# mk312_smt_main_V2a.net
KiCad netlist of a schematic drawn in EAGLE
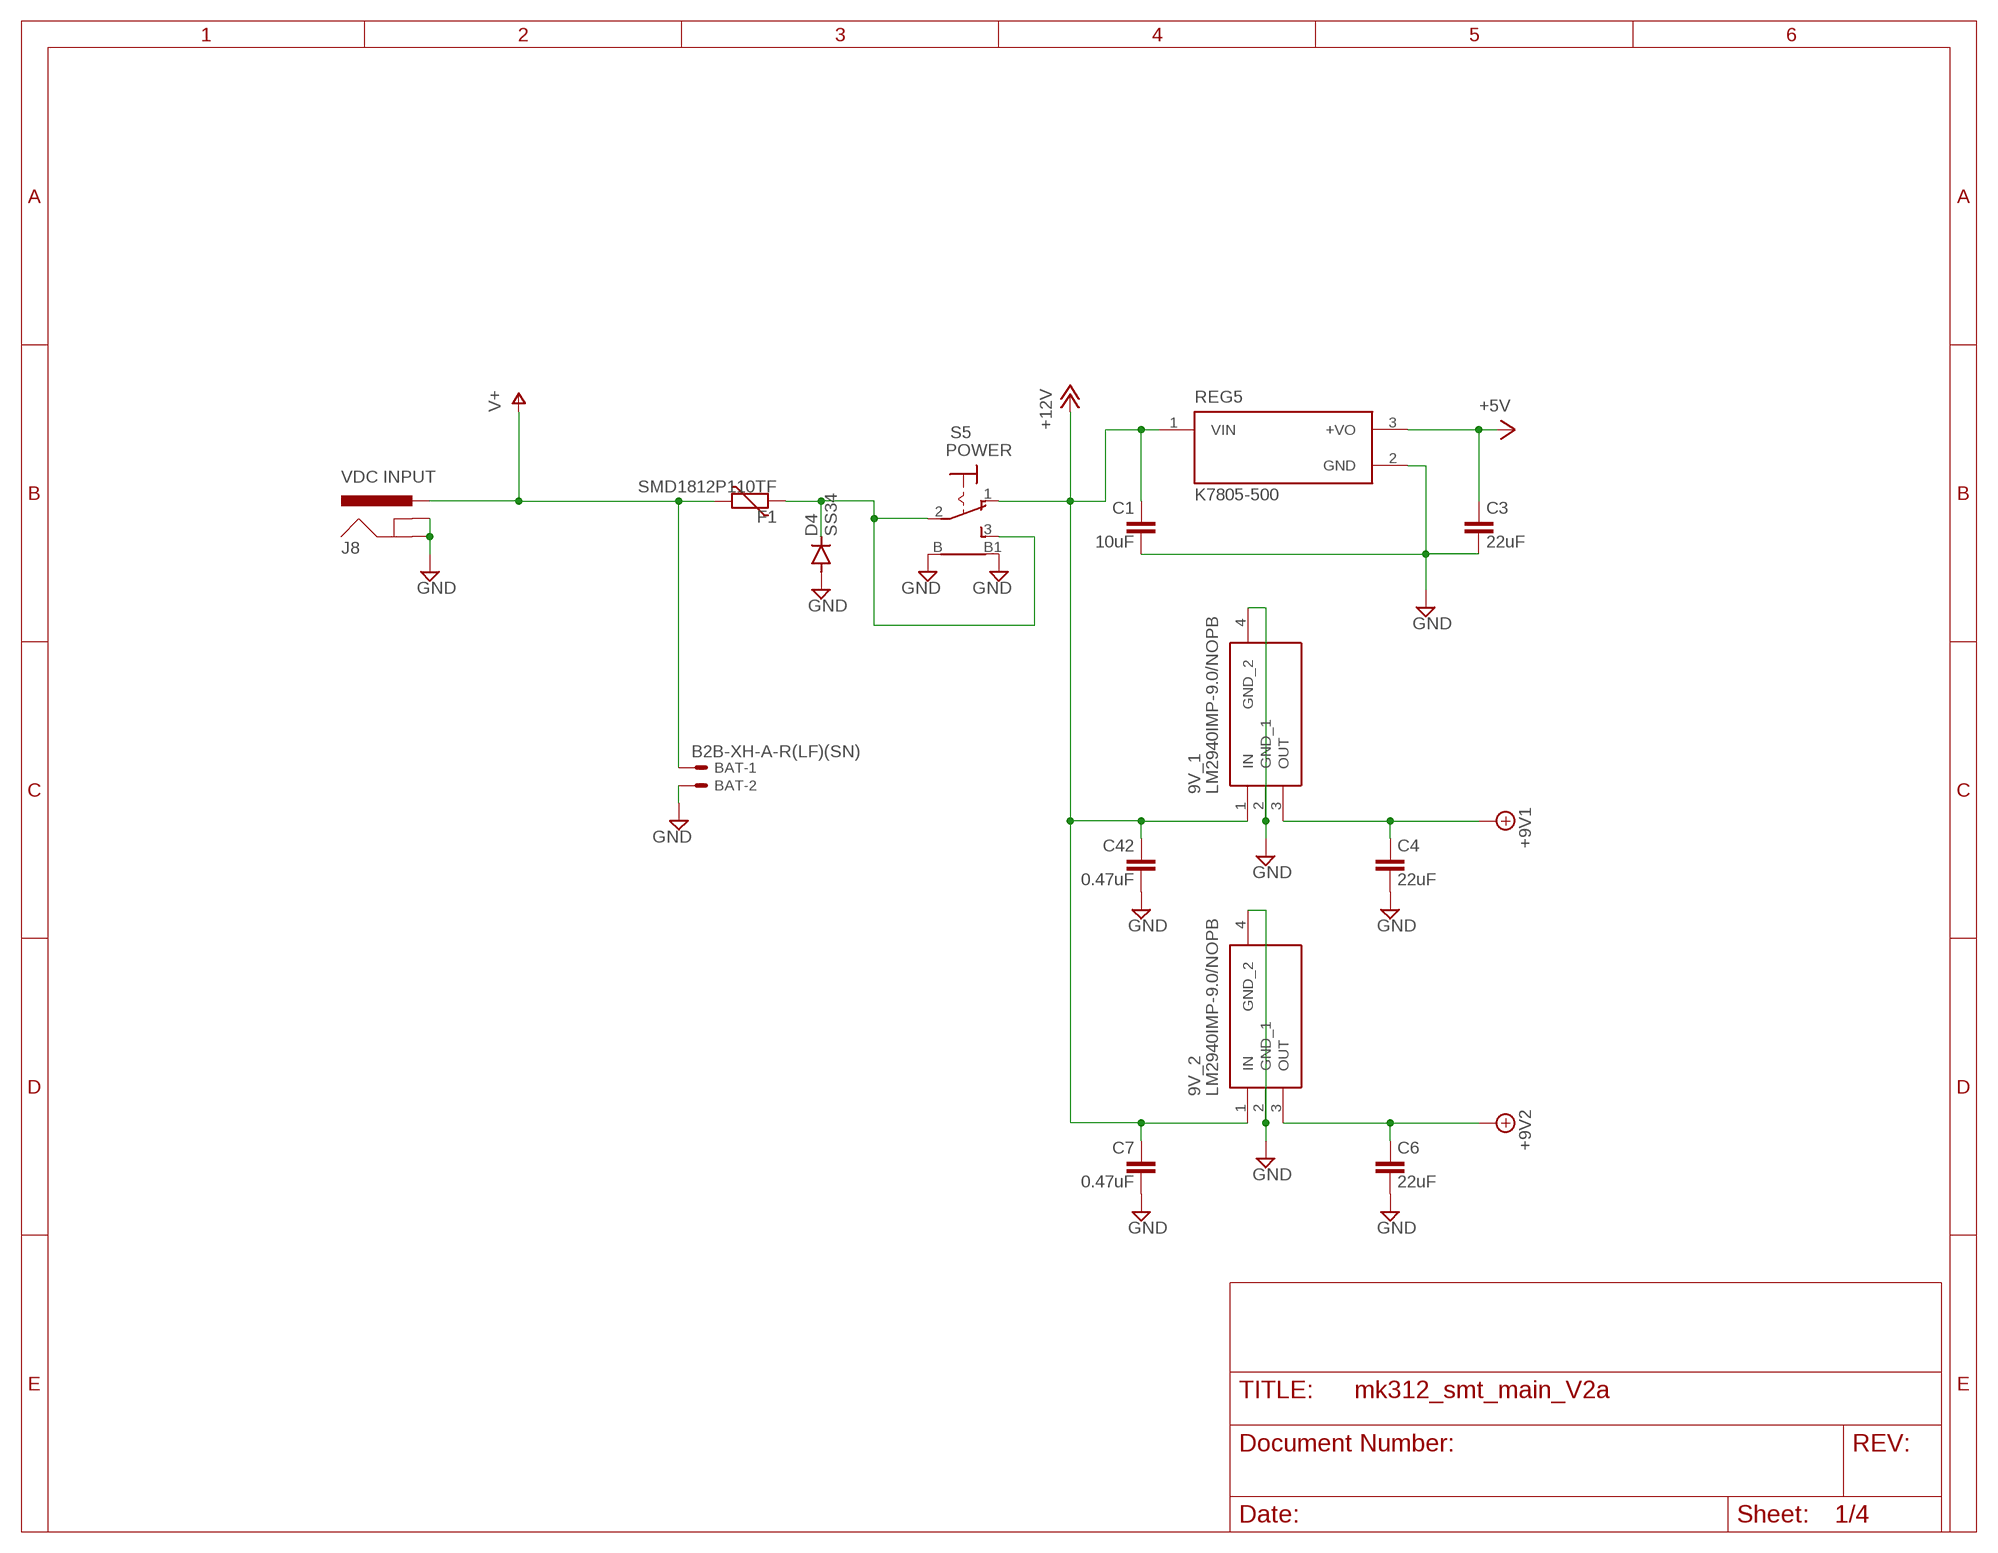
[diagram p0: schematic, sheet 1]
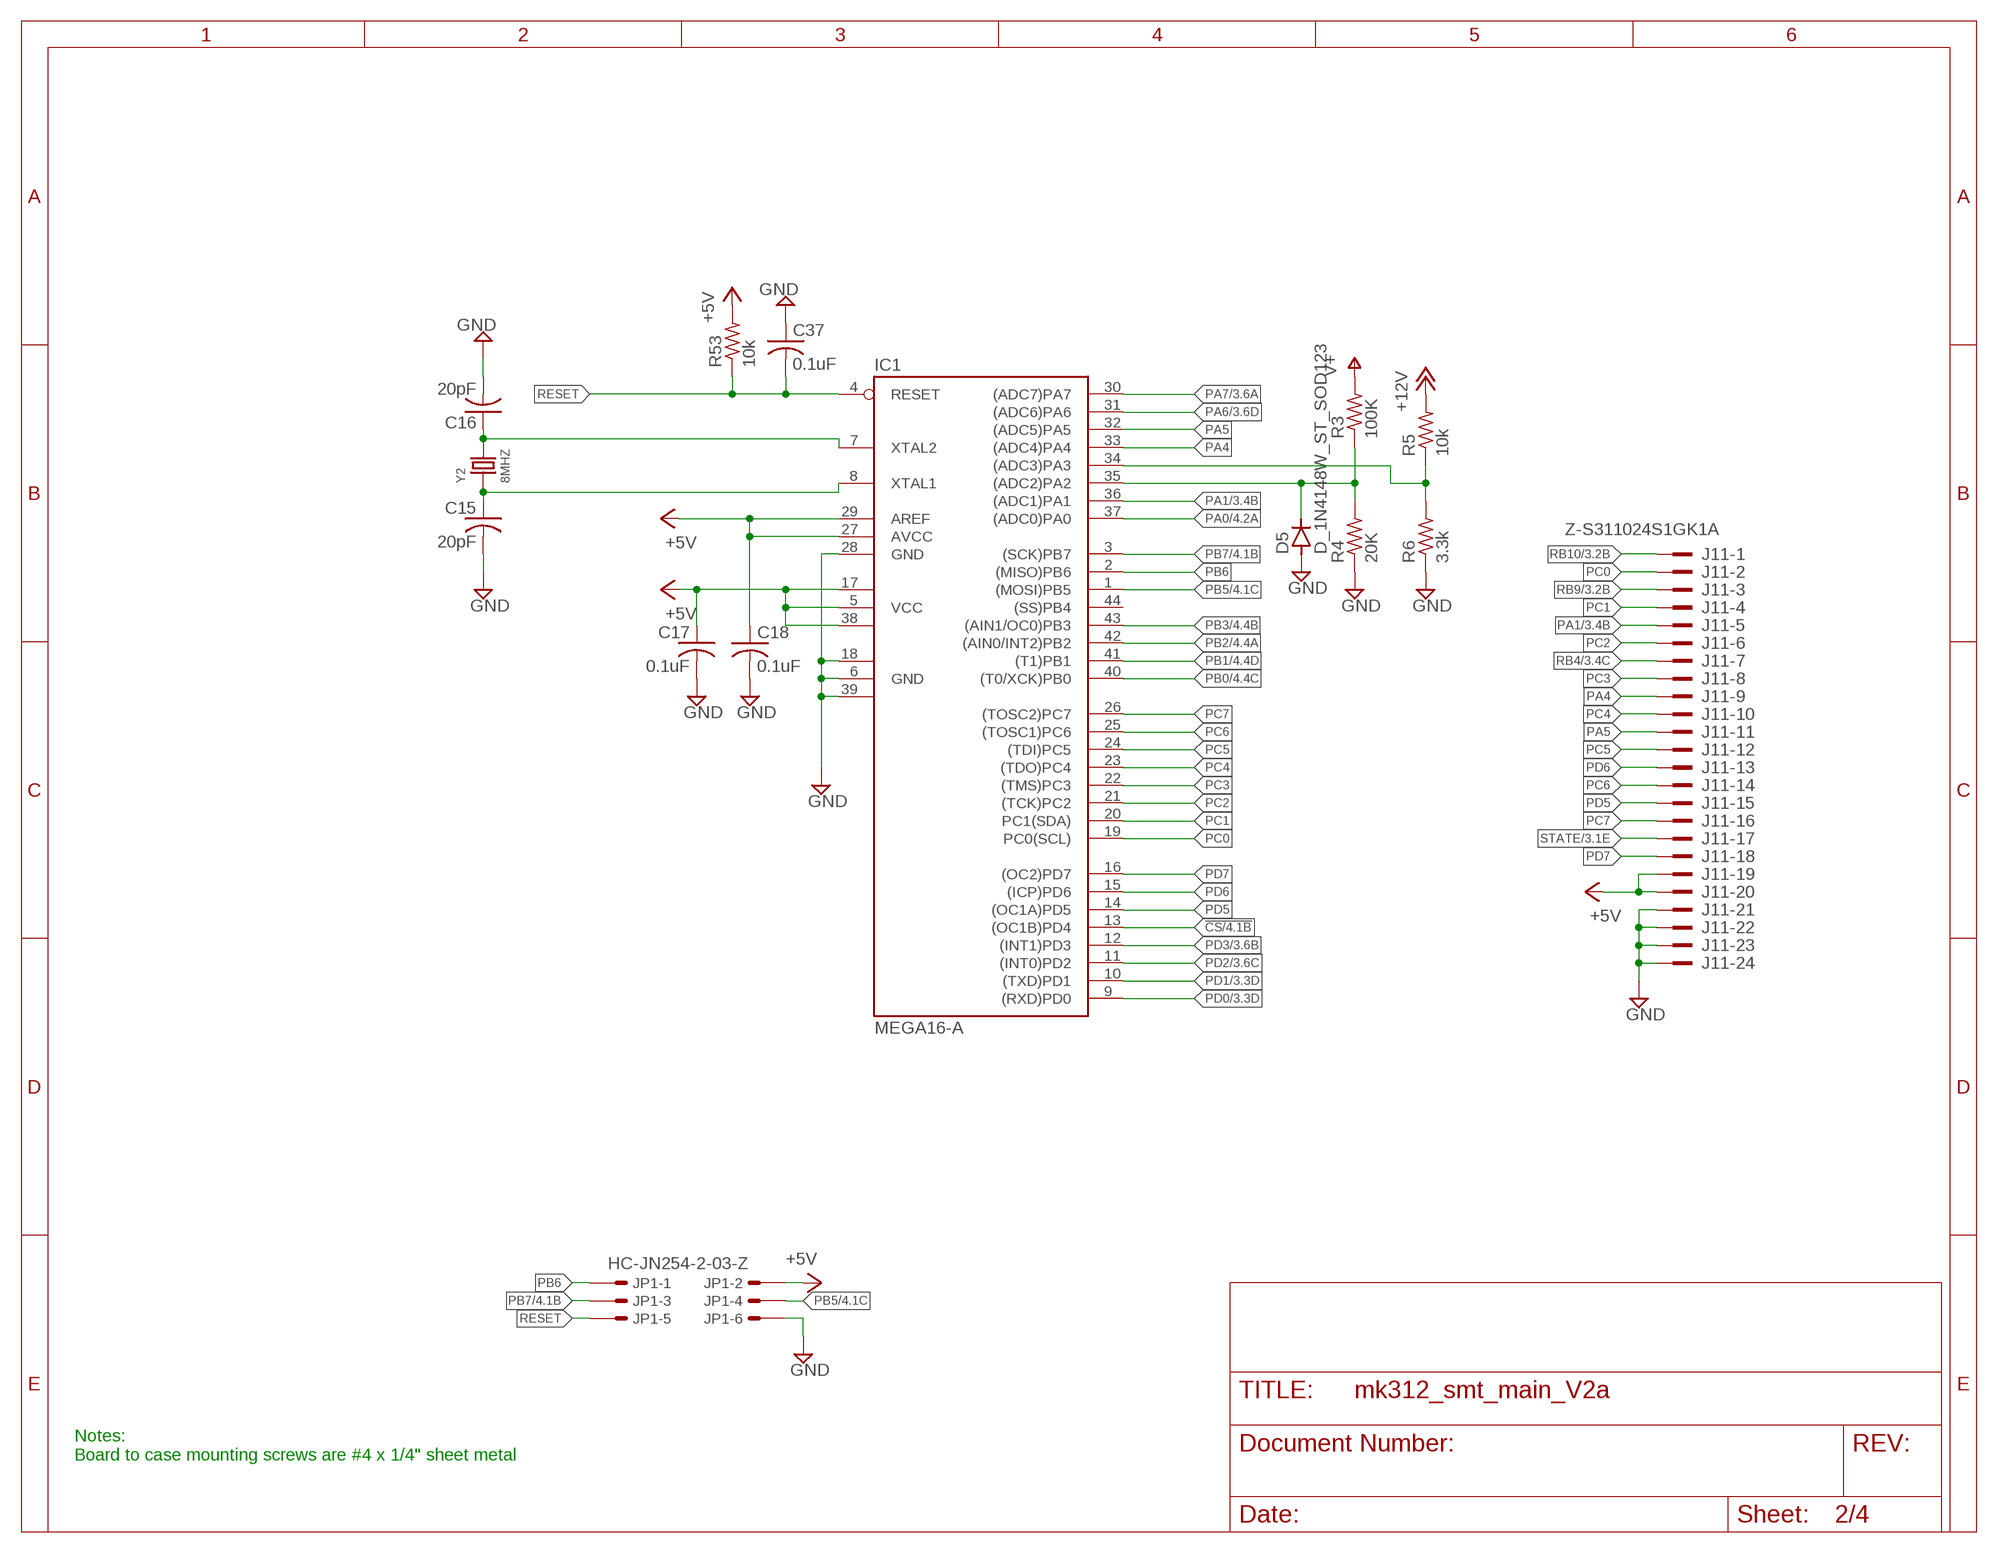
[diagram p1: schematic, sheet 2]
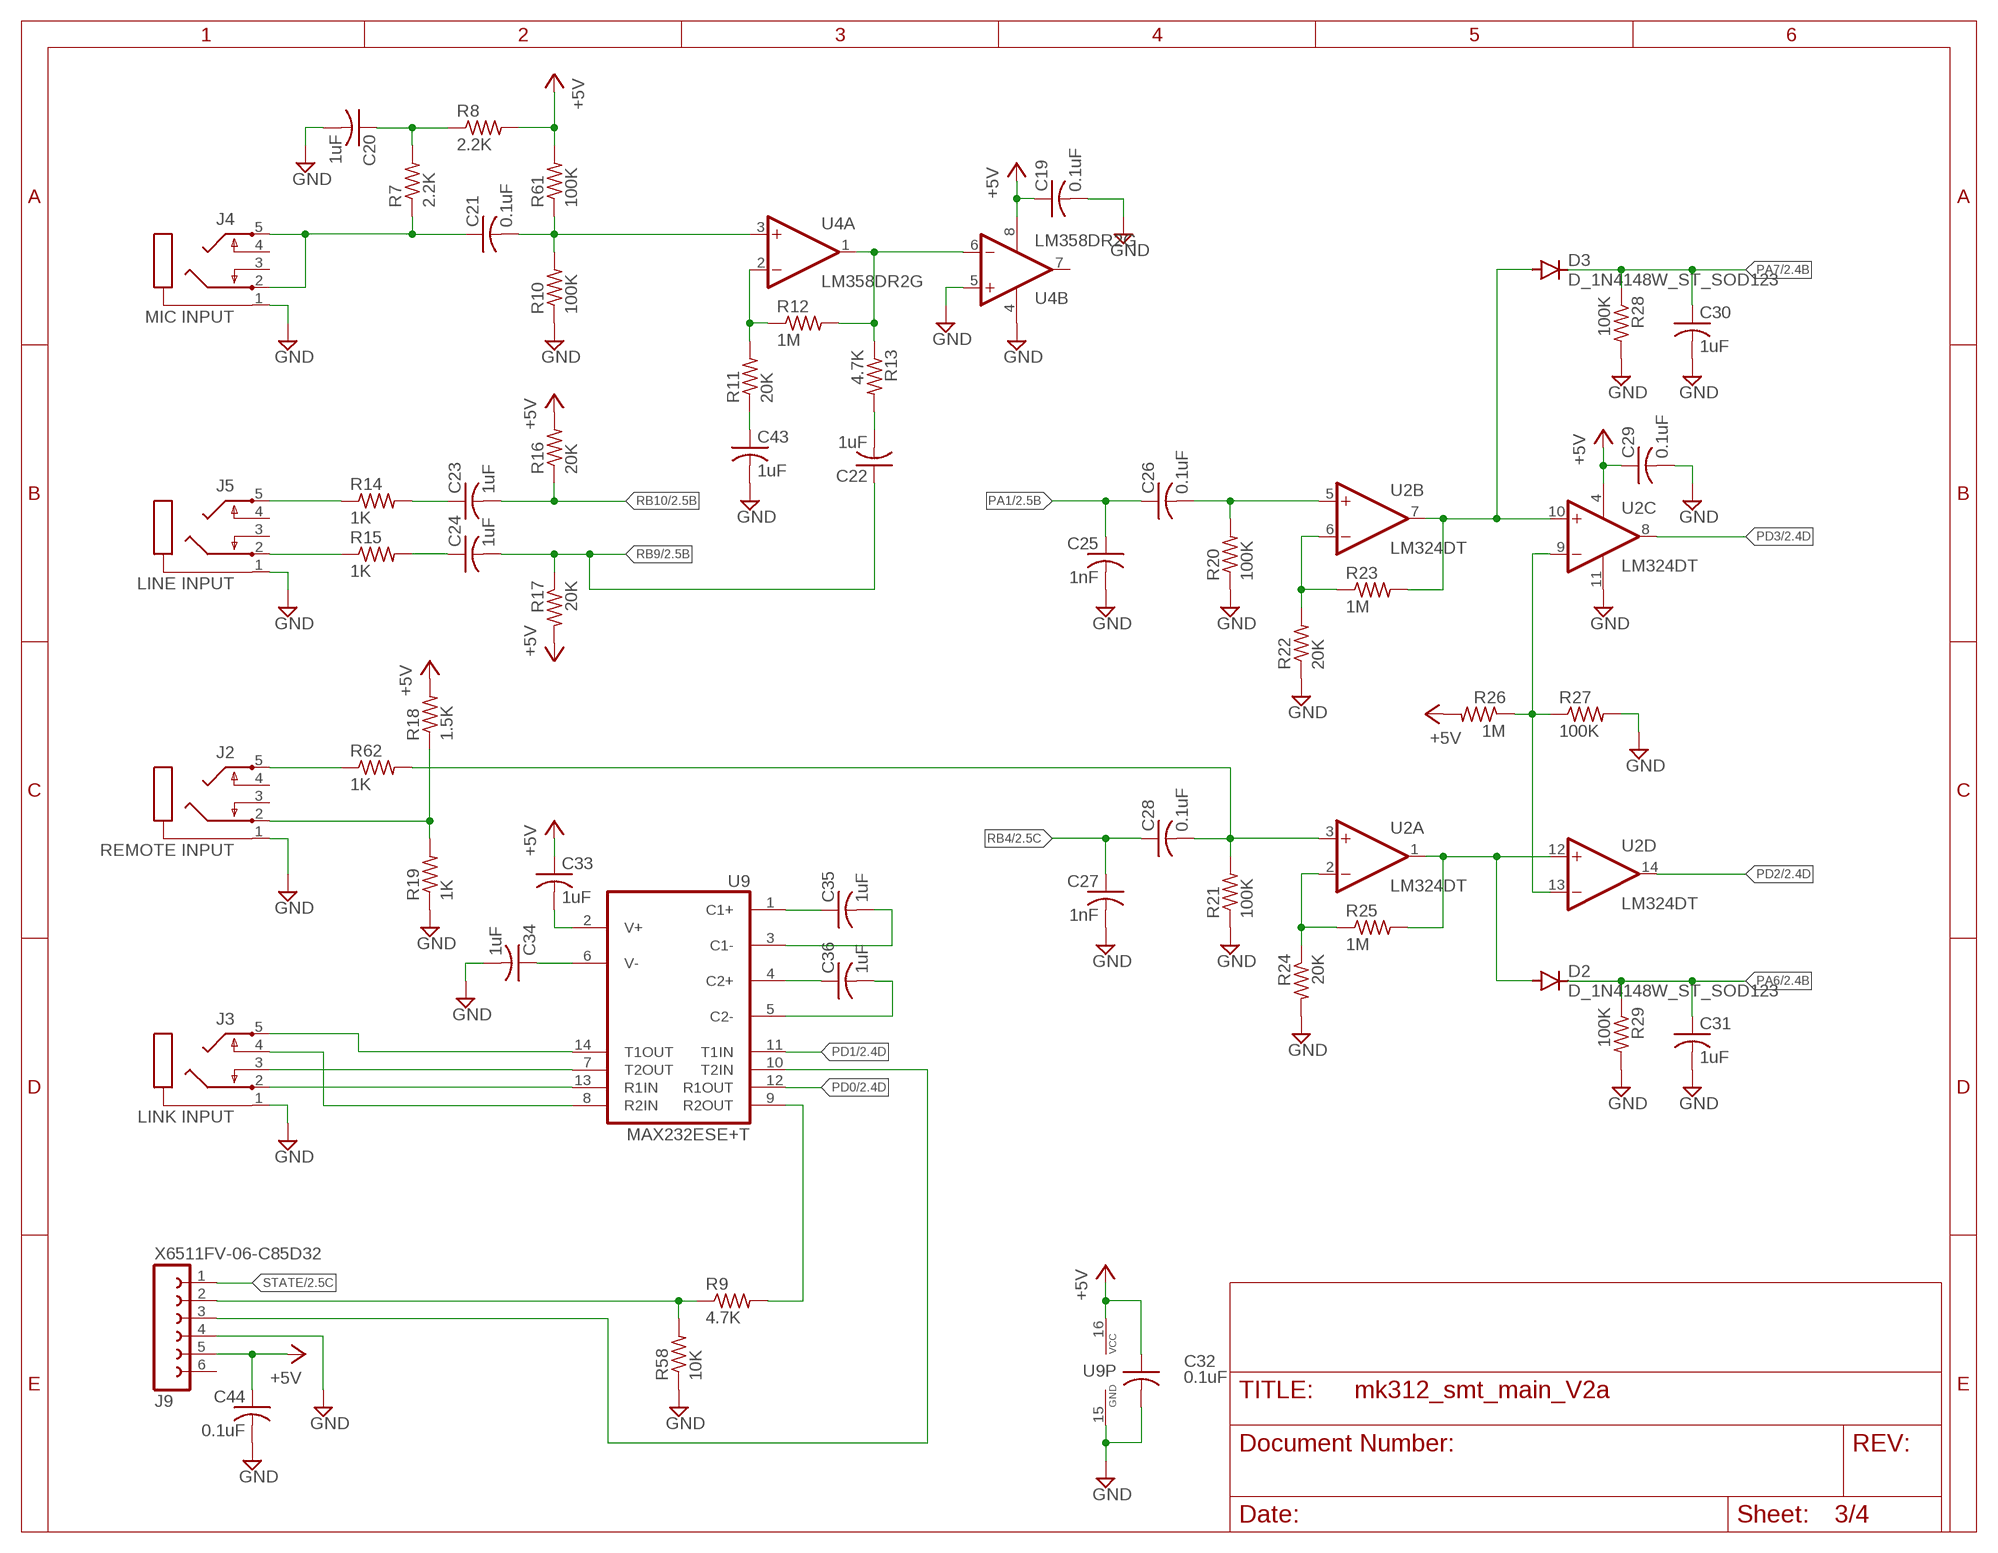
[diagram p2: schematic, sheet 3]
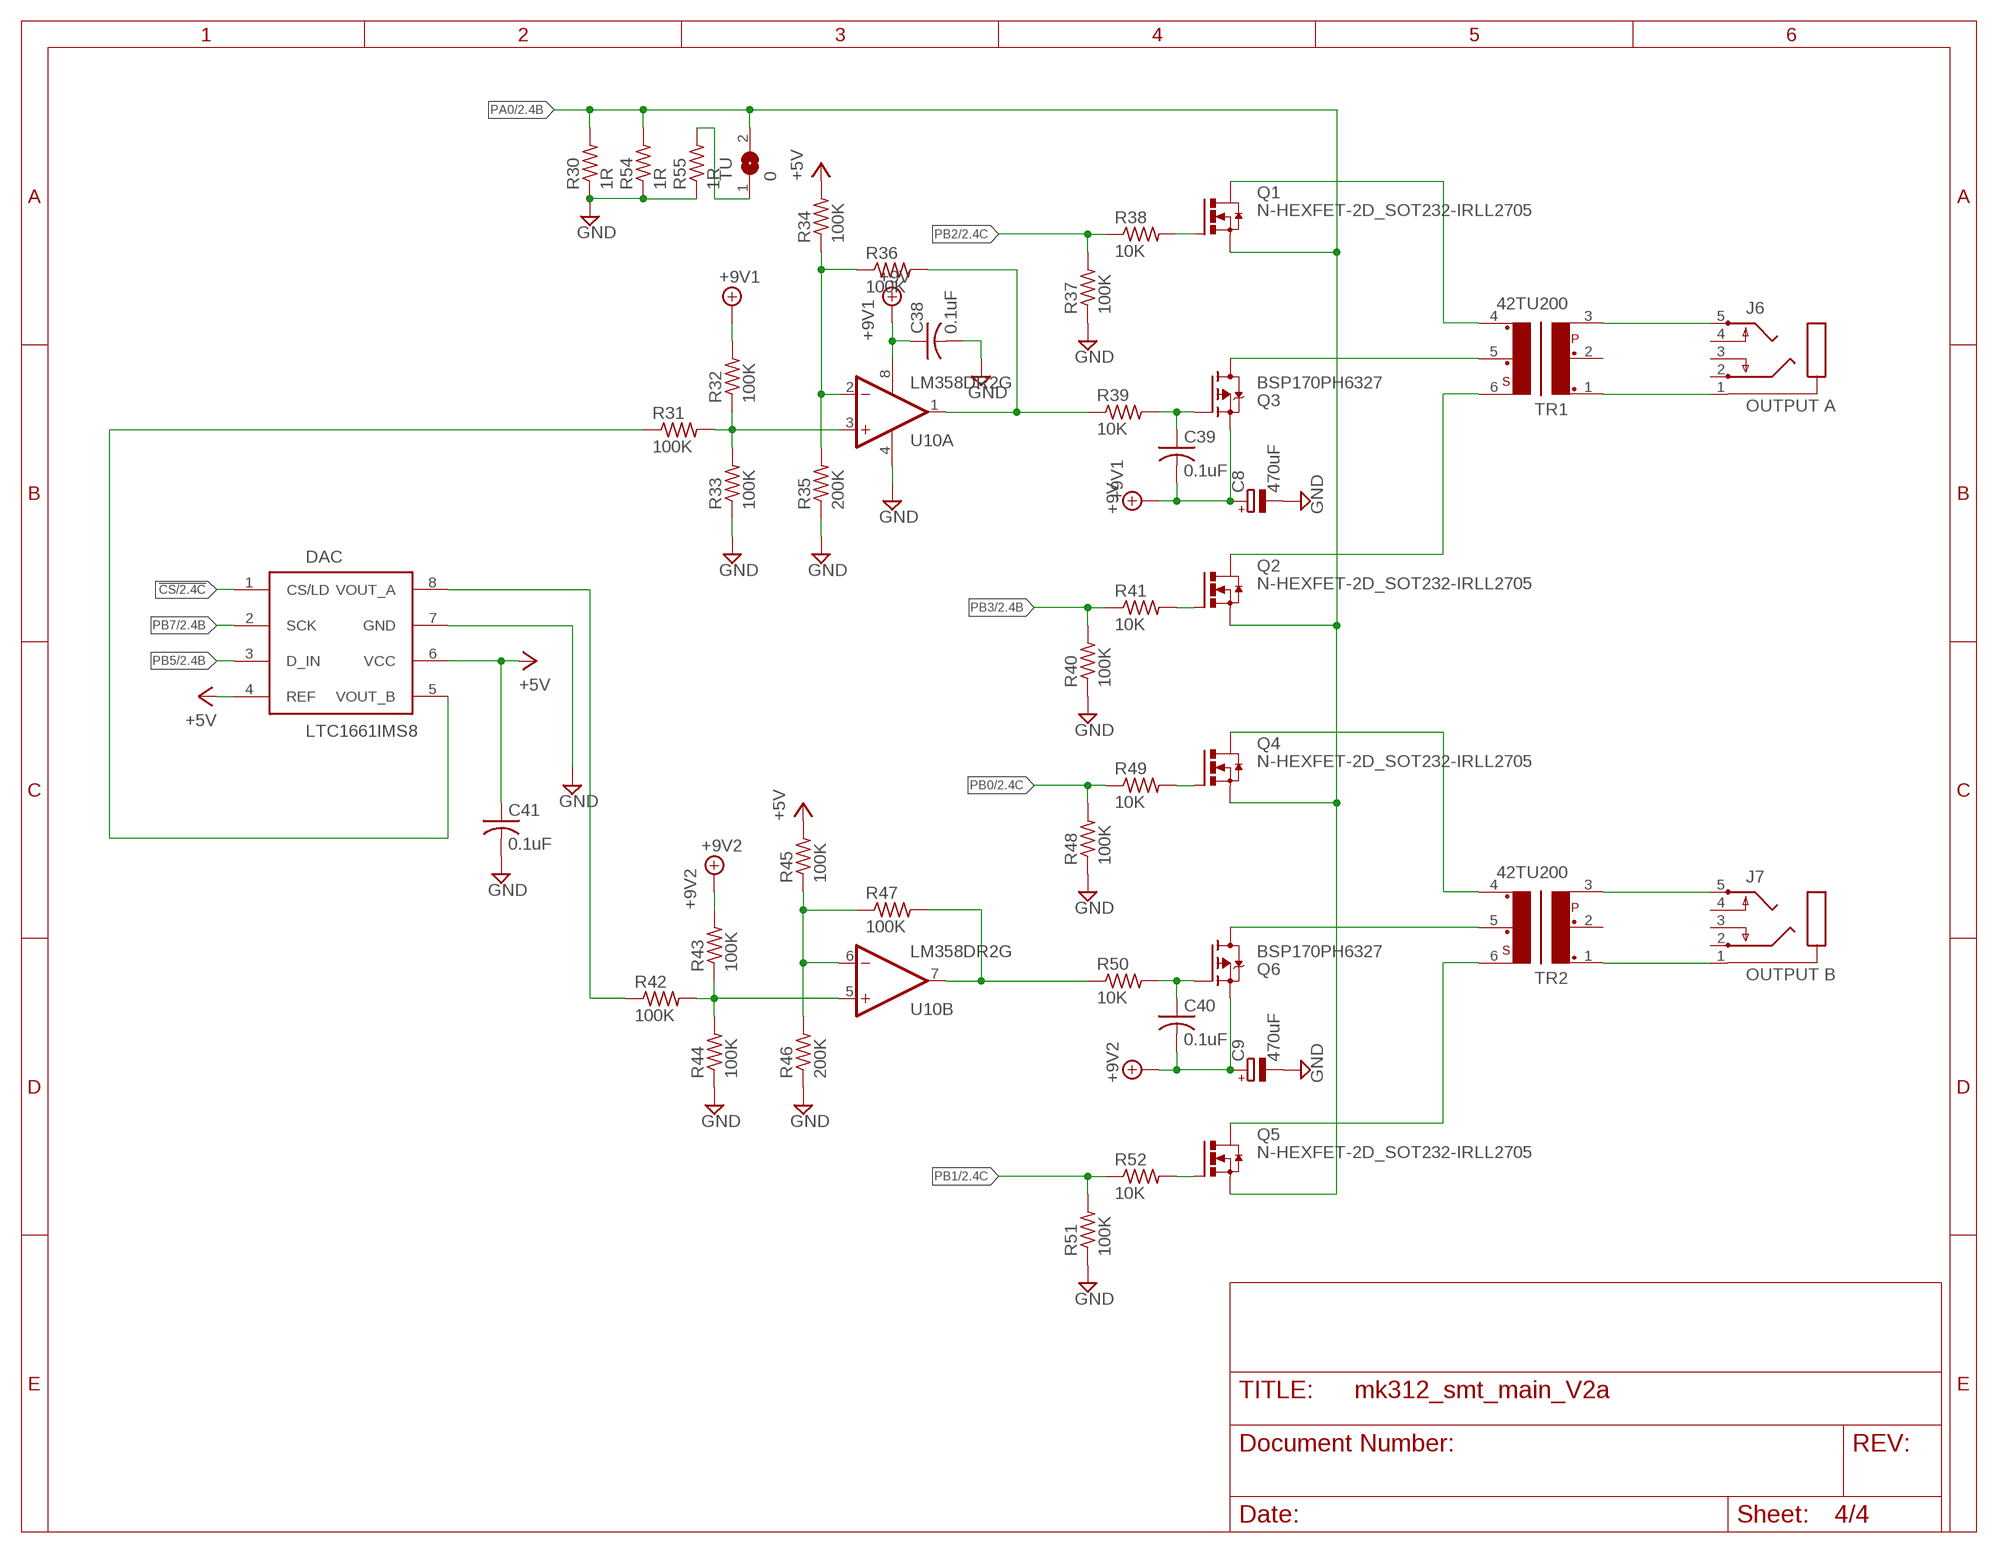
[diagram p3: schematic, sheet 4]

(export (version "E")
  (design (tool "Eeschema 10.0.6"))
  (components
    (comp (ref "C15")
      (value "20pF")
      (footprint "eagle-import:C0603")
      (libsource (lib "eagle-import") (part "C-USC0603"))
    )
    (comp (ref "C16")
      (value "20pF")
      (footprint "eagle-import:C0603")
      (libsource (lib "eagle-import") (part "C-USC0603"))
    )
    (comp (ref "C17")
      (value "0.1uF")
      (footprint "eagle-import:C0805")
      (libsource (lib "eagle-import") (part "C-USC0805"))
    )
    (comp (ref "C18")
      (value "0.1uF")
      (footprint "eagle-import:C0805")
      (libsource (lib "eagle-import") (part "C-USC0805"))
    )
    (comp (ref "C37")
      (value "0.1uF")
      (footprint "eagle-import:C0805")
      (libsource (lib "eagle-import") (part "rcl_334_C-USC0805"))
    )
    (comp (ref "D5")
      (value "D_1N4148W_ST_SOD123")
      (footprint "eagle-import:SOD123")
      (fields (field (name "LCSC_PART") "C81598"))
      (libsource (lib "eagle-import") (part "D__SOD1231N4148W_ST"))
    )
    (comp (ref "IC1")
      (value "MEGA16-A")
      (footprint "eagle-import:TQFP44")
      (fields (field (name "MPN") "ATMEGA16-16AU"))
      (libsource (lib "eagle-import") (part "MEGA16-A"))
    )
    (comp (ref "J11")
      (value "Z-S311024S1GK1A")
      (footprint "eagle-import:PAK100_2500-24")
      (libsource (lib "eagle-import") (part "2524-"))
    )
    (comp (ref "JP1")
      (value "HC-JN254-2-03-Z")
      (footprint "eagle-import:057-006-1")
      (libsource (lib "eagle-import") (part "057-006-1"))
    )
    (comp (ref "R3")
      (value "100K")
      (footprint "eagle-import:R0805")
      (libsource (lib "eagle-import") (part "R-US_R0805"))
    )
    (comp (ref "R4")
      (value "20K")
      (footprint "eagle-import:R0805")
      (libsource (lib "eagle-import") (part "R-US_R0805"))
    )
    (comp (ref "R5")
      (value "10k")
      (footprint "eagle-import:R0805")
      (libsource (lib "eagle-import") (part "R-US_R0805"))
    )
    (comp (ref "R6")
      (value "3.3k")
      (footprint "eagle-import:R0805")
      (libsource (lib "eagle-import") (part "R-US_R0805"))
    )
    (comp (ref "R53")
      (value "10k")
      (footprint "eagle-import:R0805")
      (libsource (lib "eagle-import") (part "rcl_334_R-US_R0805"))
    )
    (comp (ref "Y2")
      (value "8MHZ")
      (footprint "eagle-import:X2-SMD-5.0X3.2X1.3MM")
      (fields (field (name "MPN") "5032/2P"))
      (libsource (lib "eagle-import") (part "SMD-CRYSTAL-8MHZ-20PF-20PPM(2P-5.0X3.2MM)"))
    )
    (comp (ref "C19")
      (value "0.1uF")
      (footprint "eagle-import:C0805")
      (libsource (lib "eagle-import") (part "C-USC0805"))
    )
    (comp (ref "C20")
      (value "1uF")
      (footprint "eagle-import:C0805")
      (libsource (lib "eagle-import") (part "C-USC0805"))
    )
    (comp (ref "C21")
      (value "0.1uF")
      (footprint "eagle-import:C0805")
      (libsource (lib "eagle-import") (part "C-USC0805"))
    )
    (comp (ref "C22")
      (value "1uF")
      (footprint "eagle-import:C0805")
      (libsource (lib "eagle-import") (part "C-USC0805"))
    )
    (comp (ref "C23")
      (value "1uF")
      (footprint "eagle-import:C0805")
      (libsource (lib "eagle-import") (part "C-USC0805"))
    )
    (comp (ref "C24")
      (value "1uF")
      (footprint "eagle-import:C0805")
      (libsource (lib "eagle-import") (part "C-USC0805"))
    )
    (comp (ref "C25")
      (value "1nF")
      (footprint "eagle-import:C0805")
      (libsource (lib "eagle-import") (part "C-USC0805"))
    )
    (comp (ref "C26")
      (value "0.1uF")
      (footprint "eagle-import:C0805")
      (libsource (lib "eagle-import") (part "C-USC0805"))
    )
    (comp (ref "C27")
      (value "1nF")
      (footprint "eagle-import:C0805")
      (libsource (lib "eagle-import") (part "C-USC0805"))
    )
    (comp (ref "C28")
      (value "0.1uF")
      (footprint "eagle-import:C0805")
      (libsource (lib "eagle-import") (part "C-USC0805"))
    )
    (comp (ref "C29")
      (value "0.1uF")
      (footprint "eagle-import:C0805")
      (libsource (lib "eagle-import") (part "C-USC0805"))
    )
    (comp (ref "C30")
      (value "1uF")
      (footprint "eagle-import:C0805")
      (libsource (lib "eagle-import") (part "C-USC0805"))
    )
    (comp (ref "C31")
      (value "1uF")
      (footprint "eagle-import:C0805")
      (libsource (lib "eagle-import") (part "C-USC0805"))
    )
    (comp (ref "C32")
      (value "0.1uF")
      (footprint "eagle-import:C0805")
      (libsource (lib "eagle-import") (part "C-USC0805"))
    )
    (comp (ref "C33")
      (value "1uF")
      (footprint "eagle-import:C0805")
      (libsource (lib "eagle-import") (part "C-USC0805"))
    )
    (comp (ref "C34")
      (value "1uF")
      (footprint "eagle-import:C0805")
      (libsource (lib "eagle-import") (part "C-USC0805"))
    )
    (comp (ref "C35")
      (value "1uF")
      (footprint "eagle-import:C0805")
      (libsource (lib "eagle-import") (part "C-USC0805"))
    )
    (comp (ref "C36")
      (value "1uF")
      (footprint "eagle-import:C0805")
      (libsource (lib "eagle-import") (part "C-USC0805"))
    )
    (comp (ref "C43")
      (value "1uF")
      (footprint "eagle-import:C0805")
      (libsource (lib "eagle-import") (part "C-USC0805"))
    )
    (comp (ref "C44")
      (value "0.1uF")
      (footprint "eagle-import:C0805")
      (libsource (lib "eagle-import") (part "C-USC0805"))
    )
    (comp (ref "D2")
      (value "D_1N4148W_ST_SOD123")
      (footprint "eagle-import:SOD123")
      (fields (field (name "LCSC_PART") "C81598"))
      (libsource (lib "eagle-import") (part "D__SOD1231N4148W_ST"))
    )
    (comp (ref "D3")
      (value "D_1N4148W_ST_SOD123")
      (footprint "eagle-import:SOD123")
      (fields (field (name "LCSC_PART") "C81598"))
      (libsource (lib "eagle-import") (part "D__SOD1231N4148W_ST"))
    )
    (comp (ref "J2")
      (value "REMOTE INPUT")
      (footprint "eagle-import:PJ-3062")
      (libsource (lib "eagle-import") (part "STEREOJACKPJ-3062"))
    )
    (comp (ref "J3")
      (value "LINK INPUT")
      (footprint "eagle-import:PJ-3062")
      (libsource (lib "eagle-import") (part "STEREOJACKPJ-3062"))
    )
    (comp (ref "J4")
      (value "MIC INPUT")
      (footprint "eagle-import:PJ-3062")
      (libsource (lib "eagle-import") (part "STEREOJACKPJ-3062"))
    )
    (comp (ref "J5")
      (value "LINE INPUT")
      (footprint "eagle-import:PJ-3062")
      (libsource (lib "eagle-import") (part "STEREOJACKPJ-3062"))
    )
    (comp (ref "J9")
      (value "X6511FV-06-C85D32")
      (footprint "eagle-import:FE06")
      (libsource (lib "eagle-import") (part "FE06-1"))
    )
    (comp (ref "R7")
      (value "2.2K")
      (footprint "eagle-import:R0805")
      (libsource (lib "eagle-import") (part "R-US_R0805"))
    )
    (comp (ref "R8")
      (value "2.2K")
      (footprint "eagle-import:R0805")
      (libsource (lib "eagle-import") (part "R-US_R0805"))
    )
    (comp (ref "R9")
      (value "4.7K")
      (footprint "eagle-import:R0805")
      (libsource (lib "eagle-import") (part "R-US_R0805"))
    )
    (comp (ref "R10")
      (value "100K")
      (footprint "eagle-import:R0805")
      (libsource (lib "eagle-import") (part "R-US_R0805"))
    )
    (comp (ref "R11")
      (value "20K")
      (footprint "eagle-import:R0805")
      (libsource (lib "eagle-import") (part "R-US_R0805"))
    )
    (comp (ref "R12")
      (value "1M")
      (footprint "eagle-import:R0805")
      (libsource (lib "eagle-import") (part "R-US_R0805"))
    )
    (comp (ref "R13")
      (value "4.7K")
      (footprint "eagle-import:R0805")
      (libsource (lib "eagle-import") (part "R-US_R0805"))
    )
    (comp (ref "R14")
      (value "1K")
      (footprint "eagle-import:R0805")
      (libsource (lib "eagle-import") (part "R-US_R0805"))
    )
    (comp (ref "R15")
      (value "1K")
      (footprint "eagle-import:R0805")
      (libsource (lib "eagle-import") (part "R-US_R0805"))
    )
    (comp (ref "R16")
      (value "20K")
      (footprint "eagle-import:R0805")
      (libsource (lib "eagle-import") (part "R-US_R0805"))
    )
    (comp (ref "R17")
      (value "20K")
      (footprint "eagle-import:R0805")
      (libsource (lib "eagle-import") (part "R-US_R0805"))
    )
    (comp (ref "R18")
      (value "1.5K")
      (footprint "eagle-import:R0805")
      (libsource (lib "eagle-import") (part "R-US_R0805"))
    )
    (comp (ref "R19")
      (value "1K")
      (footprint "eagle-import:R0805")
      (libsource (lib "eagle-import") (part "R-US_R0805"))
    )
    (comp (ref "R20")
      (value "100K")
      (footprint "eagle-import:R0805")
      (libsource (lib "eagle-import") (part "R-US_R0805"))
    )
    (comp (ref "R21")
      (value "100K")
      (footprint "eagle-import:R0805")
      (libsource (lib "eagle-import") (part "R-US_R0805"))
    )
    (comp (ref "R22")
      (value "20K")
      (footprint "eagle-import:R0805")
      (libsource (lib "eagle-import") (part "R-US_R0805"))
    )
    (comp (ref "R23")
      (value "1M")
      (footprint "eagle-import:R0805")
      (libsource (lib "eagle-import") (part "R-US_R0805"))
    )
    (comp (ref "R24")
      (value "20K")
      (footprint "eagle-import:R0805")
      (libsource (lib "eagle-import") (part "R-US_R0805"))
    )
    (comp (ref "R25")
      (value "1M")
      (footprint "eagle-import:R0805")
      (libsource (lib "eagle-import") (part "R-US_R0805"))
    )
    (comp (ref "R26")
      (value "1M")
      (footprint "eagle-import:R0805")
      (libsource (lib "eagle-import") (part "R-US_R0805"))
    )
    (comp (ref "R27")
      (value "100K")
      (footprint "eagle-import:R0805")
      (libsource (lib "eagle-import") (part "R-US_R0805"))
    )
    (comp (ref "R28")
      (value "100K")
      (footprint "eagle-import:R0805")
      (libsource (lib "eagle-import") (part "R-US_R0805"))
    )
    (comp (ref "R29")
      (value "100K")
      (footprint "eagle-import:R0805")
      (libsource (lib "eagle-import") (part "R-US_R0805"))
    )
    (comp (ref "R58")
      (value "10K")
      (footprint "eagle-import:R0805")
      (libsource (lib "eagle-import") (part "R-US_R0805"))
    )
    (comp (ref "R61")
      (value "100K")
      (footprint "eagle-import:R0805")
      (libsource (lib "eagle-import") (part "R-US_R0805"))
    )
    (comp (ref "R62")
      (value "1K")
      (footprint "eagle-import:R0805")
      (libsource (lib "eagle-import") (part "R-US_R0805"))
    )
    (comp (ref "U2")
      (value "LM324DT")
      (footprint "eagle-import:SO14")
      (libsource (lib "eagle-import") (part "LM324D"))
    )
    (comp (ref "U4")
      (value "LM358DR2G")
      (footprint "eagle-import:SO08")
      (libsource (lib "eagle-import") (part "LM358D"))
    )
    (comp (ref "U9")
      (value "MAX232ESE+T")
      (footprint "eagle-import:SOP-16")
      (libsource (lib "eagle-import") (part "MAX232ECWESOP16"))
    )
    (comp (ref "9V_1")
      (value "LM2940IMP-9.0/NOPB")
      (footprint "eagle-import:SOT230P700X180-4N")
      (fields (field (name "MOUSER_PART_NUMBER") "926-LM2940IMP90NOPB"))
      (libsource (lib "eagle-import") (part "LM2940IMP-9.0_NOPB"))
    )
    (comp (ref "9V_2")
      (value "LM2940IMP-9.0/NOPB")
      (footprint "eagle-import:SOT230P700X180-4N")
      (fields (field (name "MOUSER_PART_NUMBER") "926-LM2940IMP90NOPB"))
      (libsource (lib "eagle-import") (part "LM2940IMP-9.0_NOPB"))
    )
    (comp (ref "BAT")
      (value "B2B-XH-A-R(LF)(SN)")
      (footprint "eagle-import:JST-XH-02-PACKAGE-LONG-PAD")
      (libsource (lib "eagle-import") (part "JST-XH-02-PIN-LONG-PAD"))
    )
    (comp (ref "C1")
      (value "10uF")
      (footprint "eagle-import:C0805")
      (libsource (lib "eagle-import") (part "C-EUC0805"))
    )
    (comp (ref "C3")
      (value "22uF")
      (footprint "eagle-import:C1206")
      (libsource (lib "eagle-import") (part "C-EUC1206"))
    )
    (comp (ref "C4")
      (value "22uF")
      (footprint "eagle-import:C1206")
      (libsource (lib "eagle-import") (part "C-EUC1206"))
    )
    (comp (ref "C6")
      (value "22uF")
      (footprint "eagle-import:C1206")
      (libsource (lib "eagle-import") (part "C-EUC1206"))
    )
    (comp (ref "C7")
      (value "0.47uF")
      (footprint "eagle-import:C0805")
      (libsource (lib "eagle-import") (part "C-EUC0805"))
    )
    (comp (ref "C42")
      (value "0.47uF")
      (footprint "eagle-import:C0805")
      (libsource (lib "eagle-import") (part "C-EUC0805"))
    )
    (comp (ref "D4")
      (value "SS34")
      (footprint "eagle-import:SMA")
      (libsource (lib "eagle-import") (part "S1M"))
    )
    (comp (ref "F1")
      (value "SMD1812P110TF")
      (footprint "eagle-import:CT_CN1812")
      (libsource (lib "eagle-import") (part "VARISTORCN1812"))
    )
    (comp (ref "J8")
      (value "VDC INPUT")
      (footprint "eagle-import:POWER_JACK_SLOT")
      (libsource (lib "eagle-import") (part "POWER_JACKSLT"))
    )
    (comp (ref "REG5")
      (value "K7805-500")
      (footprint "eagle-import:CONV_K7809M-1000R3")
      (fields (field (name "MF") "Mornsun America, LLC") (field (name "MP") "K7809M-1000R3"))
      (libsource (lib "eagle-import") (part "K7809M-1000R3"))
    )
    (comp (ref "S5")
      (value "POWER")
      (footprint "eagle-import:LPV-1")
      (libsource (lib "eagle-import") (part "LPV-1"))
    )
    (comp (ref "C8")
      (value "470uF")
      (footprint "eagle-import:150CLZ-1010")
      (libsource (lib "eagle-import") (part "CPOL-EU150CLZ-1010"))
    )
    (comp (ref "C9")
      (value "470uF")
      (footprint "eagle-import:150CLZ-1010")
      (libsource (lib "eagle-import") (part "CPOL-EU150CLZ-1010"))
    )
    (comp (ref "C38")
      (value "0.1uF")
      (footprint "eagle-import:C0805")
      (libsource (lib "eagle-import") (part "C-USC0805"))
    )
    (comp (ref "C39")
      (value "0.1uF")
      (footprint "eagle-import:C0805")
      (libsource (lib "eagle-import") (part "C-USC0805"))
    )
    (comp (ref "C40")
      (value "0.1uF")
      (footprint "eagle-import:C0805")
      (libsource (lib "eagle-import") (part "C-USC0805"))
    )
    (comp (ref "C41")
      (value "0.1uF")
      (footprint "eagle-import:C0805")
      (libsource (lib "eagle-import") (part "C-USC0805"))
    )
    (comp (ref "DAC")
      (value "LTC1661IMS8")
      (footprint "eagle-import:MSOP8")
      (libsource (lib "eagle-import") (part "LTC1661IMS8"))
    )
    (comp (ref "J6")
      (value "OUTPUT A")
      (footprint "eagle-import:PJ-3062")
      (libsource (lib "eagle-import") (part "STEREOJACKPJ-3062"))
    )
    (comp (ref "J7")
      (value "OUTPUT B")
      (footprint "eagle-import:PJ-3062")
      (libsource (lib "eagle-import") (part "STEREOJACKPJ-3062"))
    )
    (comp (ref "Q1")
      (value "N-HEXFET-2D_SOT232-IRLL2705")
      (footprint "eagle-import:SOT223")
      (libsource (lib "eagle-import") (part "N-HEXFET-2D_?-SOT232IRLL2705"))
    )
    (comp (ref "Q2")
      (value "N-HEXFET-2D_SOT232-IRLL2705")
      (footprint "eagle-import:SOT223")
      (libsource (lib "eagle-import") (part "N-HEXFET-2D_?-SOT232IRLL2705"))
    )
    (comp (ref "Q3")
      (value "BSP170PH6327")
      (footprint "eagle-import:SOT230P700X180-4N")
      (libsource (lib "eagle-import") (part "IRFL9014TRPBF"))
    )
    (comp (ref "Q4")
      (value "N-HEXFET-2D_SOT232-IRLL2705")
      (footprint "eagle-import:SOT223")
      (libsource (lib "eagle-import") (part "N-HEXFET-2D_?-SOT232IRLL2705"))
    )
    (comp (ref "Q5")
      (value "N-HEXFET-2D_SOT232-IRLL2705")
      (footprint "eagle-import:SOT223")
      (libsource (lib "eagle-import") (part "N-HEXFET-2D_?-SOT232IRLL2705"))
    )
    (comp (ref "Q6")
      (value "BSP170PH6327")
      (footprint "eagle-import:SOT230P700X180-4N")
      (libsource (lib "eagle-import") (part "IRFL9014TRPBF"))
    )
    (comp (ref "R30")
      (value "1R")
      (footprint "eagle-import:R1206")
      (libsource (lib "eagle-import") (part "R-US_R1206"))
    )
    (comp (ref "R31")
      (value "100K")
      (footprint "eagle-import:R0805")
      (libsource (lib "eagle-import") (part "R-US_R0805"))
    )
    (comp (ref "R32")
      (value "100K")
      (footprint "eagle-import:R0805")
      (libsource (lib "eagle-import") (part "R-US_R0805"))
    )
    (comp (ref "R33")
      (value "100K")
      (footprint "eagle-import:R0805")
      (libsource (lib "eagle-import") (part "R-US_R0805"))
    )
    (comp (ref "R34")
      (value "100K")
      (footprint "eagle-import:R0805")
      (libsource (lib "eagle-import") (part "R-US_R0805"))
    )
    (comp (ref "R35")
      (value "200K")
      (footprint "eagle-import:R0805")
      (libsource (lib "eagle-import") (part "R-US_R0805"))
    )
    (comp (ref "R36")
      (value "100K")
      (footprint "eagle-import:R0805")
      (libsource (lib "eagle-import") (part "R-US_R0805"))
    )
    (comp (ref "R37")
      (value "100K")
      (footprint "eagle-import:R0805")
      (libsource (lib "eagle-import") (part "R-US_R0805"))
    )
    (comp (ref "R38")
      (value "10K")
      (footprint "eagle-import:R0805")
      (libsource (lib "eagle-import") (part "R-US_R0805"))
    )
    (comp (ref "R39")
      (value "10K")
      (footprint "eagle-import:R0805")
      (libsource (lib "eagle-import") (part "R-US_R0805"))
    )
    (comp (ref "R40")
      (value "100K")
      (footprint "eagle-import:R0805")
      (libsource (lib "eagle-import") (part "R-US_R0805"))
    )
    (comp (ref "R41")
      (value "10K")
      (footprint "eagle-import:R0805")
      (libsource (lib "eagle-import") (part "R-US_R0805"))
    )
    (comp (ref "R42")
      (value "100K")
      (footprint "eagle-import:R0805")
      (libsource (lib "eagle-import") (part "R-US_R0805"))
    )
    (comp (ref "R43")
      (value "100K")
      (footprint "eagle-import:R0805")
      (libsource (lib "eagle-import") (part "R-US_R0805"))
    )
    (comp (ref "R44")
      (value "100K")
      (footprint "eagle-import:R0805")
      (libsource (lib "eagle-import") (part "R-US_R0805"))
    )
    (comp (ref "R45")
      (value "100K")
      (footprint "eagle-import:R0805")
      (libsource (lib "eagle-import") (part "R-US_R0805"))
    )
    (comp (ref "R46")
      (value "200K")
      (footprint "eagle-import:R0805")
      (libsource (lib "eagle-import") (part "R-US_R0805"))
    )
    (comp (ref "R47")
      (value "100K")
      (footprint "eagle-import:R0805")
      (libsource (lib "eagle-import") (part "R-US_R0805"))
    )
    (comp (ref "R48")
      (value "100K")
      (footprint "eagle-import:R0805")
      (libsource (lib "eagle-import") (part "R-US_R0805"))
    )
    (comp (ref "R49")
      (value "10K")
      (footprint "eagle-import:R0805")
      (libsource (lib "eagle-import") (part "R-US_R0805"))
    )
    (comp (ref "R50")
      (value "10K")
      (footprint "eagle-import:R0805")
      (libsource (lib "eagle-import") (part "R-US_R0805"))
    )
    (comp (ref "R51")
      (value "100K")
      (footprint "eagle-import:R0805")
      (libsource (lib "eagle-import") (part "R-US_R0805"))
    )
    (comp (ref "R52")
      (value "10K")
      (footprint "eagle-import:R0805")
      (libsource (lib "eagle-import") (part "R-US_R0805"))
    )
    (comp (ref "R54")
      (value "1R")
      (footprint "eagle-import:R1206")
      (libsource (lib "eagle-import") (part "R-US_R1206"))
    )
    (comp (ref "R55")
      (value "1R")
      (footprint "eagle-import:R1206")
      (libsource (lib "eagle-import") (part "R-US_R1206"))
    )
    (comp (ref "TR1")
      (value "42TU200")
      (footprint "eagle-import:42TL")
      (libsource (lib "eagle-import") (part "42T?42TU"))
    )
    (comp (ref "TR2")
      (value "42TU200")
      (footprint "eagle-import:42TL")
      (libsource (lib "eagle-import") (part "42T?42TU"))
    )
    (comp (ref "TU") (value "0") (footprint "eagle-import:SJ") (libsource (lib "eagle-import") (part "SJ")))
    (comp (ref "U10")
      (value "LM358DR2G")
      (footprint "eagle-import:SO08")
      (libsource (lib "eagle-import") (part "LM358D"))
    )
  )
  (nets
    (net (code "1") (name "+5V") (class "Default")
      (node (ref "C17") (pin "1") (pinfunction "1_1") (pintype "passive"))
      (node (ref "C18") (pin "1") (pinfunction "1_1") (pintype "passive"))
      (node (ref "C19") (pin "1") (pinfunction "1_1") (pintype "passive"))
      (node (ref "C29") (pin "1") (pinfunction "1_1") (pintype "passive"))
      (node (ref "C3") (pin "1") (pinfunction "1_1") (pintype "passive"))
      (node (ref "C32") (pin "1") (pinfunction "1_1") (pintype "passive"))
      (node (ref "C33") (pin "1") (pinfunction "1_1") (pintype "passive"))
      (node (ref "C41") (pin "1") (pinfunction "1_1") (pintype "passive"))
      (node (ref "C44") (pin "1") (pinfunction "1_1") (pintype "passive"))
      (node (ref "DAC") (pin "4") (pinfunction "REF_4") (pintype "input"))
      (node (ref "DAC") (pin "6") (pinfunction "VCC_6") (pintype "power_in"))
      (node (ref "IC1") (pin "17") (pinfunction "VCC1_17") (pintype "power_in"))
      (node (ref "IC1") (pin "27") (pinfunction "AVCC_27") (pintype "power_in"))
      (node (ref "IC1") (pin "29") (pinfunction "AREF_29") (pintype "passive"))
      (node (ref "IC1") (pin "38") (pinfunction "VCC2_38") (pintype "power_in"))
      (node (ref "IC1") (pin "5") (pinfunction "VCC_5") (pintype "power_in"))
      (node (ref "J11") (pin "19") (pinfunction "KL_19") (pintype "passive"))
      (node (ref "J11") (pin "20") (pinfunction "KL_20") (pintype "passive"))
      (node (ref "J9") (pin "5") (pinfunction "5_5") (pintype "passive"))
      (node (ref "JP1") (pin "2") (pinfunction "S_2") (pintype "passive"))
      (node (ref "R16") (pin "2") (pinfunction "2_2") (pintype "passive"))
      (node (ref "R17") (pin "2") (pinfunction "2_2") (pintype "passive"))
      (node (ref "R18") (pin "2") (pinfunction "2_2") (pintype "passive"))
      (node (ref "R26") (pin "2") (pinfunction "2_2") (pintype "passive"))
      (node (ref "R34") (pin "2") (pinfunction "2_2") (pintype "passive"))
      (node (ref "R45") (pin "2") (pinfunction "2_2") (pintype "passive"))
      (node (ref "R53") (pin "2") (pinfunction "2_2") (pintype "passive"))
      (node (ref "R61") (pin "2") (pinfunction "2_2") (pintype "passive"))
      (node (ref "R8") (pin "2") (pinfunction "2_2") (pintype "passive"))
      (node (ref "REG5") (pin "3") (pinfunction "+VO_3") (pintype "output"))
      (node (ref "U2") (pin "4") (pinfunction "V+_4") (pintype "power_in"))
      (node (ref "U4") (pin "8") (pinfunction "V+_8") (pintype "power_in"))
      (node (ref "U9") (pin "16") (pinfunction "VCC_16") (pintype "power_in"))
    )
    (net (code "2") (name "+9V1") (class "Default")
      (node (ref "9V_1") (pin "3") (pinfunction "OUT_3") (pintype "power_in"))
      (node (ref "C38") (pin "1") (pinfunction "1_1") (pintype "passive"))
      (node (ref "C39") (pin "2") (pinfunction "2_2") (pintype "passive"))
      (node (ref "C4") (pin "1") (pinfunction "1_1") (pintype "passive"))
      (node (ref "C8") (pin "+") (pinfunction "+_+") (pintype "passive"))
      (node (ref "Q3") (pin "3") (pinfunction "S_3") (pintype "passive"))
      (node (ref "R32") (pin "2") (pinfunction "2_2") (pintype "passive"))
      (node (ref "U10") (pin "8") (pinfunction "V+_8") (pintype "power_in"))
    )
    (net (code "3") (name "+9V2") (class "Default")
      (node (ref "9V_2") (pin "3") (pinfunction "OUT_3") (pintype "power_in"))
      (node (ref "C40") (pin "2") (pinfunction "2_2") (pintype "passive"))
      (node (ref "C6") (pin "1") (pinfunction "1_1") (pintype "passive"))
      (node (ref "C9") (pin "+") (pinfunction "+_+") (pintype "passive"))
      (node (ref "Q6") (pin "3") (pinfunction "S_3") (pintype "passive"))
      (node (ref "R43") (pin "2") (pinfunction "2_2") (pintype "passive"))
    )
    (net (code "4") (name "+12V") (class "Default")
      (node (ref "9V_1") (pin "1") (pinfunction "IN_1") (pintype "input"))
      (node (ref "9V_2") (pin "1") (pinfunction "IN_1") (pintype "input"))
      (node (ref "C1") (pin "1") (pinfunction "1_1") (pintype "passive"))
      (node (ref "C42") (pin "1") (pinfunction "1_1") (pintype "passive"))
      (node (ref "C7") (pin "1") (pinfunction "1_1") (pintype "passive"))
      (node (ref "R5") (pin "2") (pinfunction "2_2") (pintype "passive"))
      (node (ref "REG5") (pin "1") (pinfunction "VIN_1") (pintype "input"))
      (node (ref "S5") (pin "1") (pinfunction "O_1") (pintype "passive"))
    )
    (net (code "5") (name "GND") (class "Default")
      (node (ref "9V_1") (pin "2") (pinfunction "GND_1_2") (pintype "power_in"))
      (node (ref "9V_1") (pin "4") (pinfunction "GND_2_4") (pintype "power_in"))
      (node (ref "9V_2") (pin "2") (pinfunction "GND_1_2") (pintype "power_in"))
      (node (ref "9V_2") (pin "4") (pinfunction "GND_2_4") (pintype "power_in"))
      (node (ref "BAT") (pin "2") (pinfunction "S_2") (pintype "passive"))
      (node (ref "C1") (pin "2") (pinfunction "2_2") (pintype "passive"))
      (node (ref "C15") (pin "2") (pinfunction "2_2") (pintype "passive"))
      (node (ref "C16") (pin "2") (pinfunction "2_2") (pintype "passive"))
      (node (ref "C17") (pin "2") (pinfunction "2_2") (pintype "passive"))
      (node (ref "C18") (pin "2") (pinfunction "2_2") (pintype "passive"))
      (node (ref "C19") (pin "2") (pinfunction "2_2") (pintype "passive"))
      (node (ref "C20") (pin "2") (pinfunction "2_2") (pintype "passive"))
      (node (ref "C25") (pin "2") (pinfunction "2_2") (pintype "passive"))
      (node (ref "C27") (pin "2") (pinfunction "2_2") (pintype "passive"))
      (node (ref "C29") (pin "2") (pinfunction "2_2") (pintype "passive"))
      (node (ref "C3") (pin "2") (pinfunction "2_2") (pintype "passive"))
      (node (ref "C30") (pin "2") (pinfunction "2_2") (pintype "passive"))
      (node (ref "C31") (pin "2") (pinfunction "2_2") (pintype "passive"))
      (node (ref "C32") (pin "2") (pinfunction "2_2") (pintype "passive"))
      (node (ref "C34") (pin "2") (pinfunction "2_2") (pintype "passive"))
      (node (ref "C37") (pin "1") (pinfunction "1_1") (pintype "passive"))
      (node (ref "C38") (pin "2") (pinfunction "2_2") (pintype "passive"))
      (node (ref "C4") (pin "2") (pinfunction "2_2") (pintype "passive"))
      (node (ref "C41") (pin "2") (pinfunction "2_2") (pintype "passive"))
      (node (ref "C42") (pin "2") (pinfunction "2_2") (pintype "passive"))
      (node (ref "C43") (pin "2") (pinfunction "2_2") (pintype "passive"))
      (node (ref "C44") (pin "2") (pinfunction "2_2") (pintype "passive"))
      (node (ref "C6") (pin "2") (pinfunction "2_2") (pintype "passive"))
      (node (ref "C7") (pin "2") (pinfunction "2_2") (pintype "passive"))
      (node (ref "C8") (pin "-") (pinfunction "-_-") (pintype "passive"))
      (node (ref "C9") (pin "-") (pinfunction "-_-") (pintype "passive"))
      (node (ref "D4") (pin "A") (pinfunction "A_A") (pintype "passive"))
      (node (ref "D5") (pin "A") (pinfunction "A_A") (pintype "passive"))
      (node (ref "DAC") (pin "7") (pinfunction "GND_7") (pintype "power_in"))
      (node (ref "IC1") (pin "18") (pinfunction "GND1_18") (pintype "power_in"))
      (node (ref "IC1") (pin "28") (pinfunction "GND_28") (pintype "power_in"))
      (node (ref "IC1") (pin "39") (pinfunction "GND2_39") (pintype "power_in"))
      (node (ref "IC1") (pin "6") (pinfunction "GND_6") (pintype "power_in"))
      (node (ref "J11") (pin "21") (pinfunction "KL_21") (pintype "passive"))
      (node (ref "J11") (pin "22") (pinfunction "KL_22") (pintype "passive"))
      (node (ref "J11") (pin "23") (pinfunction "KL_23") (pintype "passive"))
      (node (ref "J11") (pin "24") (pinfunction "KL_24") (pintype "passive"))
      (node (ref "J2") (pin "1") (pinfunction "1_1") (pintype "passive"))
      (node (ref "J3") (pin "1") (pinfunction "1_1") (pintype "passive"))
      (node (ref "J4") (pin "1") (pinfunction "1_1") (pintype "passive"))
      (node (ref "J5") (pin "1") (pinfunction "1_1") (pintype "passive"))
      (node (ref "J8") (pin "GND@1") (pinfunction "GNDBREAK_GND@1") (pintype "bidirectional"))
      (node (ref "J8") (pin "GND@2") (pinfunction "GND_GND@2") (pintype "bidirectional"))
      (node (ref "J9") (pin "4") (pinfunction "4_4") (pintype "passive"))
      (node (ref "JP1") (pin "6") (pinfunction "S_6") (pintype "passive"))
      (node (ref "R10") (pin "1") (pinfunction "1_1") (pintype "passive"))
      (node (ref "R19") (pin "1") (pinfunction "1_1") (pintype "passive"))
      (node (ref "R20") (pin "1") (pinfunction "1_1") (pintype "passive"))
      (node (ref "R21") (pin "1") (pinfunction "1_1") (pintype "passive"))
      (node (ref "R22") (pin "1") (pinfunction "1_1") (pintype "passive"))
      (node (ref "R24") (pin "2") (pinfunction "2_2") (pintype "passive"))
      (node (ref "R27") (pin "2") (pinfunction "2_2") (pintype "passive"))
      (node (ref "R28") (pin "2") (pinfunction "2_2") (pintype "passive"))
      (node (ref "R29") (pin "2") (pinfunction "2_2") (pintype "passive"))
      (node (ref "R30") (pin "1") (pinfunction "1_1") (pintype "passive"))
      (node (ref "R33") (pin "1") (pinfunction "1_1") (pintype "passive"))
      (node (ref "R35") (pin "1") (pinfunction "1_1") (pintype "passive"))
      (node (ref "R37") (pin "1") (pinfunction "1_1") (pintype "passive"))
      (node (ref "R4") (pin "1") (pinfunction "1_1") (pintype "passive"))
      (node (ref "R40") (pin "1") (pinfunction "1_1") (pintype "passive"))
      (node (ref "R44") (pin "1") (pinfunction "1_1") (pintype "passive"))
      (node (ref "R46") (pin "1") (pinfunction "1_1") (pintype "passive"))
      (node (ref "R48") (pin "1") (pinfunction "1_1") (pintype "passive"))
      (node (ref "R51") (pin "1") (pinfunction "1_1") (pintype "passive"))
      (node (ref "R54") (pin "1") (pinfunction "1_1") (pintype "passive"))
      (node (ref "R55") (pin "1") (pinfunction "1_1") (pintype "passive"))
      (node (ref "R58") (pin "1") (pinfunction "1_1") (pintype "passive"))
      (node (ref "R6") (pin "1") (pinfunction "1_1") (pintype "passive"))
      (node (ref "REG5") (pin "2") (pinfunction "GND_2") (pintype "power_in"))
      (node (ref "S5") (pin "B") (pinfunction "B_B") (pintype "passive"))
      (node (ref "S5") (pin "B1") (pinfunction "B1_B1") (pintype "passive"))
      (node (ref "U10") (pin "4") (pinfunction "V-_4") (pintype "power_in"))
      (node (ref "U2") (pin "11") (pinfunction "V-_11") (pintype "power_in"))
      (node (ref "U4") (pin "4") (pinfunction "V-_4") (pintype "power_in"))
      (node (ref "U4") (pin "5") (pinfunction "+IN_5") (pintype "input"))
      (node (ref "U9") (pin "15") (pinfunction "GND_15") (pintype "power_in"))
    )
    (net (code "6") (name "Net-(C20-Pad1)") (class "Default")
      (node (ref "C20") (pin "1") (pinfunction "1_1") (pintype "passive"))
      (node (ref "R7") (pin "2") (pinfunction "2_2") (pintype "passive"))
      (node (ref "R8") (pin "1") (pinfunction "1_1") (pintype "passive"))
    )
    (net (code "7") (name "Net-(C21-Pad1)") (class "Default")
      (node (ref "C21") (pin "1") (pinfunction "1_1") (pintype "passive"))
      (node (ref "J4") (pin "2") (pinfunction "2_2") (pintype "passive"))
      (node (ref "J4") (pin "5") (pinfunction "5_5") (pintype "passive"))
      (node (ref "R7") (pin "1") (pinfunction "1_1") (pintype "passive"))
    )
    (net (code "8") (name "Net-(C22-Pad2)") (class "Default")
      (node (ref "C22") (pin "2") (pinfunction "2_2") (pintype "passive"))
      (node (ref "R13") (pin "2") (pinfunction "2_2") (pintype "passive"))
    )
    (net (code "9") (name "Net-(C23-Pad1)") (class "Default")
      (node (ref "C23") (pin "1") (pinfunction "1_1") (pintype "passive"))
      (node (ref "R14") (pin "2") (pinfunction "2_2") (pintype "passive"))
    )
    (net (code "10") (name "Net-(C24-Pad1)") (class "Default")
      (node (ref "C24") (pin "1") (pinfunction "1_1") (pintype "passive"))
      (node (ref "R15") (pin "2") (pinfunction "2_2") (pintype "passive"))
    )
    (net (code "11") (name "Net-(C43-Pad1)") (class "Default")
      (node (ref "C43") (pin "1") (pinfunction "1_1") (pintype "passive"))
      (node (ref "R11") (pin "1") (pinfunction "1_1") (pintype "passive"))
    )
    (net (code "12") (name "Net-(DAC-VOUT_A)") (class "Default")
      (node (ref "DAC") (pin "8") (pinfunction "VOUT_A_8") (pintype "output"))
      (node (ref "R42") (pin "1") (pinfunction "1_1") (pintype "passive"))
    )
    (net (code "13") (name "Net-(DAC-VOUT_B)") (class "Default")
      (node (ref "DAC") (pin "5") (pinfunction "VOUT_B_5") (pintype "output"))
      (node (ref "R31") (pin "1") (pinfunction "1_1") (pintype "passive"))
    )
    (net (code "14") (name "Net-(IC1-(ADC2)PA2)") (class "Default")
      (node (ref "D5") (pin "C") (pinfunction "C_C") (pintype "passive"))
      (node (ref "IC1") (pin "35") (pinfunction "(ADC2)PA2_35") (pintype "bidirectional"))
      (node (ref "R3") (pin "1") (pinfunction "1_1") (pintype "passive"))
      (node (ref "R4") (pin "2") (pinfunction "2_2") (pintype "passive"))
    )
    (net (code "15") (name "Net-(IC1-(ADC3)PA3)") (class "Default")
      (node (ref "IC1") (pin "34") (pinfunction "(ADC3)PA3_34") (pintype "bidirectional"))
      (node (ref "R5") (pin "1") (pinfunction "1_1") (pintype "passive"))
      (node (ref "R6") (pin "2") (pinfunction "2_2") (pintype "passive"))
    )
    (net (code "16") (name "Net-(IC1-XTAL1)") (class "Default")
      (node (ref "C15") (pin "1") (pinfunction "1_1") (pintype "passive"))
      (node (ref "IC1") (pin "8") (pinfunction "XTAL1_8") (pintype "bidirectional"))
      (node (ref "Y2") (pin "1") (pinfunction "1_1") (pintype "passive"))
    )
    (net (code "17") (name "Net-(IC1-XTAL2)") (class "Default")
      (node (ref "C16") (pin "1") (pinfunction "1_1") (pintype "passive"))
      (node (ref "IC1") (pin "7") (pinfunction "XTAL2_7") (pintype "bidirectional"))
      (node (ref "Y2") (pin "2") (pinfunction "2_2") (pintype "passive"))
    )
    (net (code "18") (name "Net-(J2-Pad2)") (class "Default")
      (node (ref "J2") (pin "2") (pinfunction "2_2") (pintype "passive"))
      (node (ref "R18") (pin "1") (pinfunction "1_1") (pintype "passive"))
      (node (ref "R19") (pin "2") (pinfunction "2_2") (pintype "passive"))
    )
    (net (code "19") (name "Net-(J2-Pad5)") (class "Default")
      (node (ref "J2") (pin "5") (pinfunction "5_5") (pintype "passive"))
      (node (ref "R62") (pin "1") (pinfunction "1_1") (pintype "passive"))
    )
    (net (code "20") (name "Net-(J5-Pad2)") (class "Default")
      (node (ref "J5") (pin "2") (pinfunction "2_2") (pintype "passive"))
      (node (ref "R15") (pin "1") (pinfunction "1_1") (pintype "passive"))
    )
    (net (code "21") (name "Net-(J5-Pad5)") (class "Default")
      (node (ref "J5") (pin "5") (pinfunction "5_5") (pintype "passive"))
      (node (ref "R14") (pin "1") (pinfunction "1_1") (pintype "passive"))
    )
    (net (code "22") (name "Net-(J6-Pad1)") (class "Default")
      (node (ref "J6") (pin "1") (pinfunction "1_1") (pintype "passive"))
      (node (ref "TR1") (pin "1") (pinfunction "1_1") (pintype "passive"))
    )
    (net (code "23") (name "Net-(J6-Pad5)") (class "Default")
      (node (ref "J6") (pin "5") (pinfunction "5_5") (pintype "passive"))
      (node (ref "TR1") (pin "3") (pinfunction "3_3") (pintype "passive"))
    )
    (net (code "24") (name "Net-(J7-Pad1)") (class "Default")
      (node (ref "J7") (pin "1") (pinfunction "1_1") (pintype "passive"))
      (node (ref "TR2") (pin "1") (pinfunction "1_1") (pintype "passive"))
    )
    (net (code "25") (name "Net-(J7-Pad5)") (class "Default")
      (node (ref "J7") (pin "5") (pinfunction "5_5") (pintype "passive"))
      (node (ref "TR2") (pin "3") (pinfunction "3_3") (pintype "passive"))
    )
    (net (code "26") (name "Net-(J9-Pad2)") (class "Default")
      (node (ref "J9") (pin "2") (pinfunction "2_2") (pintype "passive"))
      (node (ref "R58") (pin "2") (pinfunction "2_2") (pintype "passive"))
      (node (ref "R9") (pin "1") (pinfunction "1_1") (pintype "passive"))
    )
    (net (code "27") (name "Net-(Q1-D-Pad2)") (class "Default")
      (node (ref "Q1") (pin "2") (pinfunction "D_2") (pintype "passive"))
      (node (ref "Q1") (pin "4") (pinfunction "D_4") (pintype "passive"))
      (node (ref "TR1") (pin "4") (pinfunction "4_4") (pintype "passive"))
    )
    (net (code "28") (name "Net-(Q1-G)") (class "Default")
      (node (ref "Q1") (pin "1") (pinfunction "G_1") (pintype "passive"))
      (node (ref "R38") (pin "2") (pinfunction "2_2") (pintype "passive"))
    )
    (net (code "29") (name "Net-(Q2-D-Pad2)") (class "Default")
      (node (ref "Q2") (pin "2") (pinfunction "D_2") (pintype "passive"))
      (node (ref "Q2") (pin "4") (pinfunction "D_4") (pintype "passive"))
      (node (ref "TR1") (pin "6") (pinfunction "6_6") (pintype "passive"))
    )
    (net (code "30") (name "Net-(Q2-G)") (class "Default")
      (node (ref "Q2") (pin "1") (pinfunction "G_1") (pintype "passive"))
      (node (ref "R41") (pin "2") (pinfunction "2_2") (pintype "passive"))
    )
    (net (code "31") (name "Net-(Q3-D-Pad2)") (class "Default")
      (node (ref "Q3") (pin "2") (pinfunction "D_2") (pintype "passive"))
      (node (ref "Q3") (pin "4") (pinfunction "D_4") (pintype "passive"))
      (node (ref "TR1") (pin "5") (pinfunction "5_5") (pintype "passive"))
    )
    (net (code "32") (name "Net-(Q3-G)") (class "Default")
      (node (ref "C39") (pin "1") (pinfunction "1_1") (pintype "passive"))
      (node (ref "Q3") (pin "1") (pinfunction "G_1") (pintype "passive"))
      (node (ref "R39") (pin "2") (pinfunction "2_2") (pintype "passive"))
    )
    (net (code "33") (name "Net-(Q4-D-Pad2)") (class "Default")
      (node (ref "Q4") (pin "2") (pinfunction "D_2") (pintype "passive"))
      (node (ref "Q4") (pin "4") (pinfunction "D_4") (pintype "passive"))
      (node (ref "TR2") (pin "4") (pinfunction "4_4") (pintype "passive"))
    )
    (net (code "34") (name "Net-(Q4-G)") (class "Default")
      (node (ref "Q4") (pin "1") (pinfunction "G_1") (pintype "passive"))
      (node (ref "R49") (pin "2") (pinfunction "2_2") (pintype "passive"))
    )
    (net (code "35") (name "Net-(Q5-D-Pad2)") (class "Default")
      (node (ref "Q5") (pin "2") (pinfunction "D_2") (pintype "passive"))
      (node (ref "Q5") (pin "4") (pinfunction "D_4") (pintype "passive"))
      (node (ref "TR2") (pin "6") (pinfunction "6_6") (pintype "passive"))
    )
    (net (code "36") (name "Net-(Q5-G)") (class "Default")
      (node (ref "Q5") (pin "1") (pinfunction "G_1") (pintype "passive"))
      (node (ref "R52") (pin "2") (pinfunction "2_2") (pintype "passive"))
    )
    (net (code "37") (name "Net-(Q6-D-Pad2)") (class "Default")
      (node (ref "Q6") (pin "2") (pinfunction "D_2") (pintype "passive"))
      (node (ref "Q6") (pin "4") (pinfunction "D_4") (pintype "passive"))
      (node (ref "TR2") (pin "5") (pinfunction "5_5") (pintype "passive"))
    )
    (net (code "38") (name "Net-(Q6-G)") (class "Default")
      (node (ref "C40") (pin "1") (pinfunction "1_1") (pintype "passive"))
      (node (ref "Q6") (pin "1") (pinfunction "G_1") (pintype "passive"))
      (node (ref "R50") (pin "2") (pinfunction "2_2") (pintype "passive"))
    )
    (net (code "39") (name "Net-(R55-Pad2)") (class "Default")
      (node (ref "R55") (pin "2") (pinfunction "2_2") (pintype "passive"))
      (node (ref "TU") (pin "1") (pinfunction "1_1") (pintype "passive"))
    )
    (net (code "40") (name "Net-(S5-P)") (class "Default")
      (node (ref "D4") (pin "C") (pinfunction "C_C") (pintype "passive"))
      (node (ref "F1") (pin "2") (pinfunction "2_2") (pintype "passive"))
      (node (ref "S5") (pin "2") (pinfunction "P_2") (pintype "passive"))
      (node (ref "S5") (pin "3") (pinfunction "S_3") (pintype "passive"))
    )
    (net (code "41") (name "Net-(U2A-+IN)") (class "Default")
      (node (ref "C28") (pin "2") (pinfunction "2_2") (pintype "passive"))
      (node (ref "R21") (pin "2") (pinfunction "2_2") (pintype "passive"))
      (node (ref "R62") (pin "2") (pinfunction "2_2") (pintype "passive"))
      (node (ref "U2") (pin "3") (pinfunction "+IN_3") (pintype "input"))
    )
    (net (code "42") (name "Net-(U2A--IN)") (class "Default")
      (node (ref "R24") (pin "1") (pinfunction "1_1") (pintype "passive"))
      (node (ref "R25") (pin "1") (pinfunction "1_1") (pintype "passive"))
      (node (ref "U2") (pin "2") (pinfunction "-IN_2") (pintype "input"))
    )
    (net (code "43") (name "Net-(U2A-OUT)") (class "Default")
      (node (ref "D2") (pin "A") (pinfunction "A_A") (pintype "passive"))
      (node (ref "R25") (pin "2") (pinfunction "2_2") (pintype "passive"))
      (node (ref "U2") (pin "1") (pinfunction "OUT_1") (pintype "output"))
      (node (ref "U2") (pin "12") (pinfunction "+IN_12") (pintype "input"))
    )
    (net (code "44") (name "Net-(U2B-+IN)") (class "Default")
      (node (ref "C26") (pin "2") (pinfunction "2_2") (pintype "passive"))
      (node (ref "R20") (pin "2") (pinfunction "2_2") (pintype "passive"))
      (node (ref "U2") (pin "5") (pinfunction "+IN_5") (pintype "input"))
    )
    (net (code "45") (name "Net-(U2B--IN)") (class "Default")
      (node (ref "R22") (pin "2") (pinfunction "2_2") (pintype "passive"))
      (node (ref "R23") (pin "1") (pinfunction "1_1") (pintype "passive"))
      (node (ref "U2") (pin "6") (pinfunction "-IN_6") (pintype "input"))
    )
    (net (code "46") (name "Net-(U2B-OUT)") (class "Default")
      (node (ref "D3") (pin "A") (pinfunction "A_A") (pintype "passive"))
      (node (ref "R23") (pin "2") (pinfunction "2_2") (pintype "passive"))
      (node (ref "U2") (pin "10") (pinfunction "+IN_10") (pintype "input"))
      (node (ref "U2") (pin "7") (pinfunction "OUT_7") (pintype "output"))
    )
    (net (code "47") (name "Net-(U2C--IN)") (class "Default")
      (node (ref "R26") (pin "1") (pinfunction "1_1") (pintype "passive"))
      (node (ref "R27") (pin "1") (pinfunction "1_1") (pintype "passive"))
      (node (ref "U2") (pin "13") (pinfunction "-IN_13") (pintype "input"))
      (node (ref "U2") (pin "9") (pinfunction "-IN_9") (pintype "input"))
    )
    (net (code "48") (name "Net-(U4A-+IN)") (class "Default")
      (node (ref "C21") (pin "2") (pinfunction "2_2") (pintype "passive"))
      (node (ref "R10") (pin "2") (pinfunction "2_2") (pintype "passive"))
      (node (ref "R61") (pin "1") (pinfunction "1_1") (pintype "passive"))
      (node (ref "U4") (pin "3") (pinfunction "+IN_3") (pintype "input"))
    )
    (net (code "49") (name "Net-(U4A--IN)") (class "Default")
      (node (ref "R11") (pin "2") (pinfunction "2_2") (pintype "passive"))
      (node (ref "R12") (pin "1") (pinfunction "1_1") (pintype "passive"))
      (node (ref "U4") (pin "2") (pinfunction "-IN_2") (pintype "input"))
    )
    (net (code "50") (name "Net-(U4A-OUT)") (class "Default")
      (node (ref "R12") (pin "2") (pinfunction "2_2") (pintype "passive"))
      (node (ref "R13") (pin "1") (pinfunction "1_1") (pintype "passive"))
      (node (ref "U4") (pin "1") (pinfunction "OUT_1") (pintype "output"))
      (node (ref "U4") (pin "6") (pinfunction "-IN_6") (pintype "input"))
    )
    (net (code "51") (name "Net-(U9A-C1+)") (class "Default")
      (node (ref "C35") (pin "1") (pinfunction "1_1") (pintype "passive"))
      (node (ref "U9") (pin "1") (pinfunction "C1+_1") (pintype "bidirectional"))
    )
    (net (code "52") (name "Net-(U9A-C1-)") (class "Default")
      (node (ref "C35") (pin "2") (pinfunction "2_2") (pintype "passive"))
      (node (ref "U9") (pin "3") (pinfunction "C1-_3") (pintype "bidirectional"))
    )
    (net (code "53") (name "Net-(U9A-C2+)") (class "Default")
      (node (ref "C36") (pin "1") (pinfunction "1_1") (pintype "passive"))
      (node (ref "U9") (pin "4") (pinfunction "C2+_4") (pintype "bidirectional"))
    )
    (net (code "54") (name "Net-(U9A-C2-)") (class "Default")
      (node (ref "C36") (pin "2") (pinfunction "2_2") (pintype "passive"))
      (node (ref "U9") (pin "5") (pinfunction "C2-_5") (pintype "bidirectional"))
    )
    (net (code "55") (name "Net-(U9A-R1IN)") (class "Default")
      (node (ref "J3") (pin "2") (pinfunction "2_2") (pintype "passive"))
      (node (ref "U9") (pin "13") (pinfunction "R1IN_13") (pintype "input"))
    )
    (net (code "56") (name "Net-(U9A-R2IN)") (class "Default")
      (node (ref "J3") (pin "4") (pinfunction "4_4") (pintype "passive"))
      (node (ref "U9") (pin "8") (pinfunction "R2IN_8") (pintype "input"))
    )
    (net (code "57") (name "Net-(U9A-R2OUT)") (class "Default")
      (node (ref "R9") (pin "2") (pinfunction "2_2") (pintype "passive"))
      (node (ref "U9") (pin "9") (pinfunction "R2OUT_9") (pintype "output"))
    )
    (net (code "58") (name "Net-(U9A-T1OUT)") (class "Default")
      (node (ref "J3") (pin "5") (pinfunction "5_5") (pintype "passive"))
      (node (ref "U9") (pin "14") (pinfunction "T1OUT_14") (pintype "output"))
    )
    (net (code "59") (name "Net-(U9A-T2IN)") (class "Default")
      (node (ref "J9") (pin "3") (pinfunction "3_3") (pintype "passive"))
      (node (ref "U9") (pin "10") (pinfunction "T2IN_10") (pintype "input"))
    )
    (net (code "60") (name "Net-(U9A-T2OUT)") (class "Default")
      (node (ref "J3") (pin "3") (pinfunction "3_3") (pintype "passive"))
      (node (ref "U9") (pin "7") (pinfunction "T2OUT_7") (pintype "output"))
    )
    (net (code "61") (name "Net-(U9A-V+)") (class "Default")
      (node (ref "C33") (pin "2") (pinfunction "2_2") (pintype "passive"))
      (node (ref "U9") (pin "2") (pinfunction "V+_2") (pintype "bidirectional"))
    )
    (net (code "62") (name "Net-(U9A-V-)") (class "Default")
      (node (ref "C34") (pin "1") (pinfunction "1_1") (pintype "passive"))
      (node (ref "U9") (pin "6") (pinfunction "V-_6") (pintype "bidirectional"))
    )
    (net (code "63") (name "Net-(U10A-+IN)") (class "Default")
      (node (ref "R31") (pin "2") (pinfunction "2_2") (pintype "passive"))
      (node (ref "R32") (pin "1") (pinfunction "1_1") (pintype "passive"))
      (node (ref "R33") (pin "2") (pinfunction "2_2") (pintype "passive"))
      (node (ref "U10") (pin "3") (pinfunction "+IN_3") (pintype "input"))
    )
    (net (code "64") (name "Net-(U10A--IN)") (class "Default")
      (node (ref "R34") (pin "1") (pinfunction "1_1") (pintype "passive"))
      (node (ref "R35") (pin "2") (pinfunction "2_2") (pintype "passive"))
      (node (ref "R36") (pin "1") (pinfunction "1_1") (pintype "passive"))
      (node (ref "U10") (pin "2") (pinfunction "-IN_2") (pintype "input"))
    )
    (net (code "65") (name "Net-(U10A-OUT)") (class "Default")
      (node (ref "R36") (pin "2") (pinfunction "2_2") (pintype "passive"))
      (node (ref "R39") (pin "1") (pinfunction "1_1") (pintype "passive"))
      (node (ref "U10") (pin "1") (pinfunction "OUT_1") (pintype "output"))
    )
    (net (code "66") (name "Net-(U10B-+IN)") (class "Default")
      (node (ref "R42") (pin "2") (pinfunction "2_2") (pintype "passive"))
      (node (ref "R43") (pin "1") (pinfunction "1_1") (pintype "passive"))
      (node (ref "R44") (pin "2") (pinfunction "2_2") (pintype "passive"))
      (node (ref "U10") (pin "5") (pinfunction "+IN_5") (pintype "input"))
    )
    (net (code "67") (name "Net-(U10B--IN)") (class "Default")
      (node (ref "R45") (pin "1") (pinfunction "1_1") (pintype "passive"))
      (node (ref "R46") (pin "2") (pinfunction "2_2") (pintype "passive"))
      (node (ref "R47") (pin "1") (pinfunction "1_1") (pintype "passive"))
      (node (ref "U10") (pin "6") (pinfunction "-IN_6") (pintype "input"))
    )
    (net (code "68") (name "Net-(U10B-OUT)") (class "Default")
      (node (ref "R47") (pin "2") (pinfunction "2_2") (pintype "passive"))
      (node (ref "R50") (pin "1") (pinfunction "1_1") (pintype "passive"))
      (node (ref "U10") (pin "7") (pinfunction "OUT_7") (pintype "output"))
    )
    (net (code "69") (name "PA0") (class "Default")
      (node (ref "IC1") (pin "37") (pinfunction "(ADC0)PA0_37") (pintype "bidirectional"))
      (node (ref "Q1") (pin "3") (pinfunction "S_3") (pintype "passive"))
      (node (ref "Q2") (pin "3") (pinfunction "S_3") (pintype "passive"))
      (node (ref "Q4") (pin "3") (pinfunction "S_3") (pintype "passive"))
      (node (ref "Q5") (pin "3") (pinfunction "S_3") (pintype "passive"))
      (node (ref "R30") (pin "2") (pinfunction "2_2") (pintype "passive"))
      (node (ref "R54") (pin "2") (pinfunction "2_2") (pintype "passive"))
      (node (ref "TU") (pin "2") (pinfunction "2_2") (pintype "passive"))
    )
    (net (code "70") (name "PA1") (class "Default")
      (node (ref "C25") (pin "1") (pinfunction "1_1") (pintype "passive"))
      (node (ref "C26") (pin "1") (pinfunction "1_1") (pintype "passive"))
      (node (ref "IC1") (pin "36") (pinfunction "(ADC1)PA1_36") (pintype "bidirectional"))
      (node (ref "J11") (pin "5") (pinfunction "KL_5") (pintype "passive"))
    )
    (net (code "71") (name "PA4") (class "Default")
      (node (ref "IC1") (pin "33") (pinfunction "(ADC4)PA4_33") (pintype "bidirectional"))
      (node (ref "J11") (pin "9") (pinfunction "KL_9") (pintype "passive"))
    )
    (net (code "72") (name "PA5") (class "Default")
      (node (ref "IC1") (pin "32") (pinfunction "(ADC5)PA5_32") (pintype "bidirectional"))
      (node (ref "J11") (pin "11") (pinfunction "KL_11") (pintype "passive"))
    )
    (net (code "73") (name "PA6") (class "Default")
      (node (ref "C31") (pin "1") (pinfunction "1_1") (pintype "passive"))
      (node (ref "D2") (pin "C") (pinfunction "C_C") (pintype "passive"))
      (node (ref "IC1") (pin "31") (pinfunction "(ADC6)PA6_31") (pintype "bidirectional"))
      (node (ref "R29") (pin "1") (pinfunction "1_1") (pintype "passive"))
    )
    (net (code "74") (name "PA7") (class "Default")
      (node (ref "C30") (pin "1") (pinfunction "1_1") (pintype "passive"))
      (node (ref "D3") (pin "C") (pinfunction "C_C") (pintype "passive"))
      (node (ref "IC1") (pin "30") (pinfunction "(ADC7)PA7_30") (pintype "bidirectional"))
      (node (ref "R28") (pin "1") (pinfunction "1_1") (pintype "passive"))
    )
    (net (code "75") (name "PB0") (class "Default")
      (node (ref "IC1") (pin "40") (pinfunction "(T0/XCK)PB0_40") (pintype "bidirectional"))
      (node (ref "R48") (pin "2") (pinfunction "2_2") (pintype "passive"))
      (node (ref "R49") (pin "1") (pinfunction "1_1") (pintype "passive"))
    )
    (net (code "76") (name "PB1") (class "Default")
      (node (ref "IC1") (pin "41") (pinfunction "(T1)PB1_41") (pintype "bidirectional"))
      (node (ref "R51") (pin "2") (pinfunction "2_2") (pintype "passive"))
      (node (ref "R52") (pin "1") (pinfunction "1_1") (pintype "passive"))
    )
    (net (code "77") (name "PB2") (class "Default")
      (node (ref "IC1") (pin "42") (pinfunction "(AIN0/INT2)PB2_42") (pintype "bidirectional"))
      (node (ref "R37") (pin "2") (pinfunction "2_2") (pintype "passive"))
      (node (ref "R38") (pin "1") (pinfunction "1_1") (pintype "passive"))
    )
    (net (code "78") (name "PB3") (class "Default")
      (node (ref "IC1") (pin "43") (pinfunction "(AIN1/OC0)PB3_43") (pintype "bidirectional"))
      (node (ref "R40") (pin "2") (pinfunction "2_2") (pintype "passive"))
      (node (ref "R41") (pin "1") (pinfunction "1_1") (pintype "passive"))
    )
    (net (code "79") (name "PB5") (class "Default")
      (node (ref "DAC") (pin "3") (pinfunction "D_IN_3") (pintype "input"))
      (node (ref "IC1") (pin "1") (pinfunction "(MOSI)PB5_1") (pintype "bidirectional"))
      (node (ref "JP1") (pin "4") (pinfunction "S_4") (pintype "passive"))
    )
    (net (code "80") (name "PB6") (class "Default")
      (node (ref "IC1") (pin "2") (pinfunction "(MISO)PB6_2") (pintype "bidirectional"))
      (node (ref "JP1") (pin "1") (pinfunction "S_1") (pintype "passive"))
    )
    (net (code "81") (name "PB7") (class "Default")
      (node (ref "DAC") (pin "2") (pinfunction "SCK_2") (pintype "input"))
      (node (ref "IC1") (pin "3") (pinfunction "(SCK)PB7_3") (pintype "bidirectional"))
      (node (ref "JP1") (pin "3") (pinfunction "S_3") (pintype "passive"))
    )
    (net (code "82") (name "PC0") (class "Default")
      (node (ref "IC1") (pin "19") (pinfunction "PC0(SCL)_19") (pintype "bidirectional"))
      (node (ref "J11") (pin "2") (pinfunction "KL_2") (pintype "passive"))
    )
    (net (code "83") (name "PC1") (class "Default")
      (node (ref "IC1") (pin "20") (pinfunction "PC1(SDA)_20") (pintype "bidirectional"))
      (node (ref "J11") (pin "4") (pinfunction "KL_4") (pintype "passive"))
    )
    (net (code "84") (name "PC2") (class "Default")
      (node (ref "IC1") (pin "21") (pinfunction "(TCK)PC2_21") (pintype "bidirectional"))
      (node (ref "J11") (pin "6") (pinfunction "KL_6") (pintype "passive"))
    )
    (net (code "85") (name "PC3") (class "Default")
      (node (ref "IC1") (pin "22") (pinfunction "(TMS)PC3_22") (pintype "bidirectional"))
      (node (ref "J11") (pin "8") (pinfunction "KL_8") (pintype "passive"))
    )
    (net (code "86") (name "PC4") (class "Default")
      (node (ref "IC1") (pin "23") (pinfunction "(TDO)PC4_23") (pintype "bidirectional"))
      (node (ref "J11") (pin "10") (pinfunction "KL_10") (pintype "passive"))
    )
    (net (code "87") (name "PC5") (class "Default")
      (node (ref "IC1") (pin "24") (pinfunction "(TDI)PC5_24") (pintype "bidirectional"))
      (node (ref "J11") (pin "12") (pinfunction "KL_12") (pintype "passive"))
    )
    (net (code "88") (name "PC6") (class "Default")
      (node (ref "IC1") (pin "25") (pinfunction "(TOSC1)PC6_25") (pintype "bidirectional"))
      (node (ref "J11") (pin "14") (pinfunction "KL_14") (pintype "passive"))
    )
    (net (code "89") (name "PC7") (class "Default")
      (node (ref "IC1") (pin "26") (pinfunction "(TOSC2)PC7_26") (pintype "bidirectional"))
      (node (ref "J11") (pin "16") (pinfunction "KL_16") (pintype "passive"))
    )
    (net (code "90") (name "PD0") (class "Default")
      (node (ref "IC1") (pin "9") (pinfunction "(RXD)PD0_9") (pintype "bidirectional"))
      (node (ref "U9") (pin "12") (pinfunction "R1OUT_12") (pintype "output"))
    )
    (net (code "91") (name "PD1") (class "Default")
      (node (ref "IC1") (pin "10") (pinfunction "(TXD)PD1_10") (pintype "bidirectional"))
      (node (ref "U9") (pin "11") (pinfunction "T1IN_11") (pintype "input"))
    )
    (net (code "92") (name "PD2") (class "Default")
      (node (ref "IC1") (pin "11") (pinfunction "(INT0)PD2_11") (pintype "bidirectional"))
      (node (ref "U2") (pin "14") (pinfunction "OUT_14") (pintype "output"))
    )
    (net (code "93") (name "PD3") (class "Default")
      (node (ref "IC1") (pin "12") (pinfunction "(INT1)PD3_12") (pintype "bidirectional"))
      (node (ref "U2") (pin "8") (pinfunction "OUT_8") (pintype "output"))
    )
    (net (code "94") (name "PD5") (class "Default")
      (node (ref "IC1") (pin "14") (pinfunction "(OC1A)PD5_14") (pintype "bidirectional"))
      (node (ref "J11") (pin "15") (pinfunction "KL_15") (pintype "passive"))
    )
    (net (code "95") (name "PD6") (class "Default")
      (node (ref "IC1") (pin "15") (pinfunction "(ICP)PD6_15") (pintype "bidirectional"))
      (node (ref "J11") (pin "13") (pinfunction "KL_13") (pintype "passive"))
    )
    (net (code "96") (name "PD7") (class "Default")
      (node (ref "IC1") (pin "16") (pinfunction "(OC2)PD7_16") (pintype "bidirectional"))
      (node (ref "J11") (pin "18") (pinfunction "KL_18") (pintype "passive"))
    )
    (net (code "97") (name "RB4") (class "Default")
      (node (ref "C27") (pin "1") (pinfunction "1_1") (pintype "passive"))
      (node (ref "C28") (pin "1") (pinfunction "1_1") (pintype "passive"))
      (node (ref "J11") (pin "7") (pinfunction "KL_7") (pintype "passive"))
    )
    (net (code "98") (name "RB9") (class "Default")
      (node (ref "C22") (pin "1") (pinfunction "1_1") (pintype "passive"))
      (node (ref "C24") (pin "2") (pinfunction "2_2") (pintype "passive"))
      (node (ref "J11") (pin "3") (pinfunction "KL_3") (pintype "passive"))
      (node (ref "R17") (pin "1") (pinfunction "1_1") (pintype "passive"))
    )
    (net (code "99") (name "RB10") (class "Default")
      (node (ref "C23") (pin "2") (pinfunction "2_2") (pintype "passive"))
      (node (ref "J11") (pin "1") (pinfunction "KL_1") (pintype "passive"))
      (node (ref "R16") (pin "1") (pinfunction "1_1") (pintype "passive"))
    )
    (net (code "100") (name "RESET") (class "Default")
      (node (ref "C37") (pin "2") (pinfunction "2_2") (pintype "passive"))
      (node (ref "IC1") (pin "4") (pinfunction "RESET_4") (pintype "input"))
      (node (ref "JP1") (pin "5") (pinfunction "S_5") (pintype "passive"))
      (node (ref "R53") (pin "1") (pinfunction "1_1") (pintype "passive"))
    )
    (net (code "101") (name "STATE") (class "Default")
      (node (ref "J11") (pin "17") (pinfunction "KL_17") (pintype "passive"))
      (node (ref "J9") (pin "1") (pinfunction "1_1") (pintype "passive"))
    )
    (net (code "102") (name "V+") (class "Default")
      (node (ref "BAT") (pin "1") (pinfunction "S_1") (pintype "passive"))
      (node (ref "F1") (pin "1") (pinfunction "1_1") (pintype "passive"))
      (node (ref "J8") (pin "PWR") (pinfunction "PWR_PWR") (pintype "bidirectional"))
      (node (ref "R3") (pin "2") (pinfunction "2_2") (pintype "passive"))
    )
    (net (code "103") (name "unconnected-(IC1-(SS)PB4-Pad44)") (class "Default")
      (node (ref "IC1") (pin "44") (pinfunction "(SS)PB4_44") (pintype "bidirectional"))
    )
    (net (code "104") (name "unconnected-(J2-Pad3)") (class "Default")
      (node (ref "J2") (pin "3") (pinfunction "3_3") (pintype "passive"))
    )
    (net (code "105") (name "unconnected-(J2-Pad4)") (class "Default")
      (node (ref "J2") (pin "4") (pinfunction "4_4") (pintype "passive"))
    )
    (net (code "106") (name "unconnected-(J4-Pad3)") (class "Default")
      (node (ref "J4") (pin "3") (pinfunction "3_3") (pintype "passive"))
    )
    (net (code "107") (name "unconnected-(J4-Pad4)") (class "Default")
      (node (ref "J4") (pin "4") (pinfunction "4_4") (pintype "passive"))
    )
    (net (code "108") (name "unconnected-(J5-Pad3)") (class "Default")
      (node (ref "J5") (pin "3") (pinfunction "3_3") (pintype "passive"))
    )
    (net (code "109") (name "unconnected-(J5-Pad4)") (class "Default")
      (node (ref "J5") (pin "4") (pinfunction "4_4") (pintype "passive"))
    )
    (net (code "110") (name "unconnected-(J6-Pad2)") (class "Default")
      (node (ref "J6") (pin "2") (pinfunction "2_2") (pintype "passive"))
    )
    (net (code "111") (name "unconnected-(J6-Pad3)") (class "Default")
      (node (ref "J6") (pin "3") (pinfunction "3_3") (pintype "passive"))
    )
    (net (code "112") (name "unconnected-(J6-Pad4)") (class "Default")
      (node (ref "J6") (pin "4") (pinfunction "4_4") (pintype "passive"))
    )
    (net (code "113") (name "unconnected-(J7-Pad2)") (class "Default")
      (node (ref "J7") (pin "2") (pinfunction "2_2") (pintype "passive"))
    )
    (net (code "114") (name "unconnected-(J7-Pad3)") (class "Default")
      (node (ref "J7") (pin "3") (pinfunction "3_3") (pintype "passive"))
    )
    (net (code "115") (name "unconnected-(J7-Pad4)") (class "Default")
      (node (ref "J7") (pin "4") (pinfunction "4_4") (pintype "passive"))
    )
    (net (code "116") (name "unconnected-(J9-Pad6)") (class "Default")
      (node (ref "J9") (pin "6") (pinfunction "6_6") (pintype "passive"))
    )
    (net (code "117") (name "unconnected-(TR1-Pad2)") (class "Default")
      (node (ref "TR1") (pin "2") (pinfunction "2_2") (pintype "passive"))
    )
    (net (code "118") (name "unconnected-(TR2-Pad2)") (class "Default")
      (node (ref "TR2") (pin "2") (pinfunction "2_2") (pintype "passive"))
    )
    (net (code "119") (name "unconnected-(U4B-OUT-Pad7)") (class "Default")
      (node (ref "U4") (pin "7") (pinfunction "OUT_7") (pintype "output"))
    )
    (net (code "120") (name "~{CS}") (class "Default")
      (node (ref "DAC") (pin "1") (pinfunction "CS/LD_1") (pintype "input"))
      (node (ref "IC1") (pin "13") (pinfunction "(OC1B)PD4_13") (pintype "bidirectional"))
    )
  )
)
